# io-board-a-7.net
KiCad netlist of a schematic drawn in EAGLE
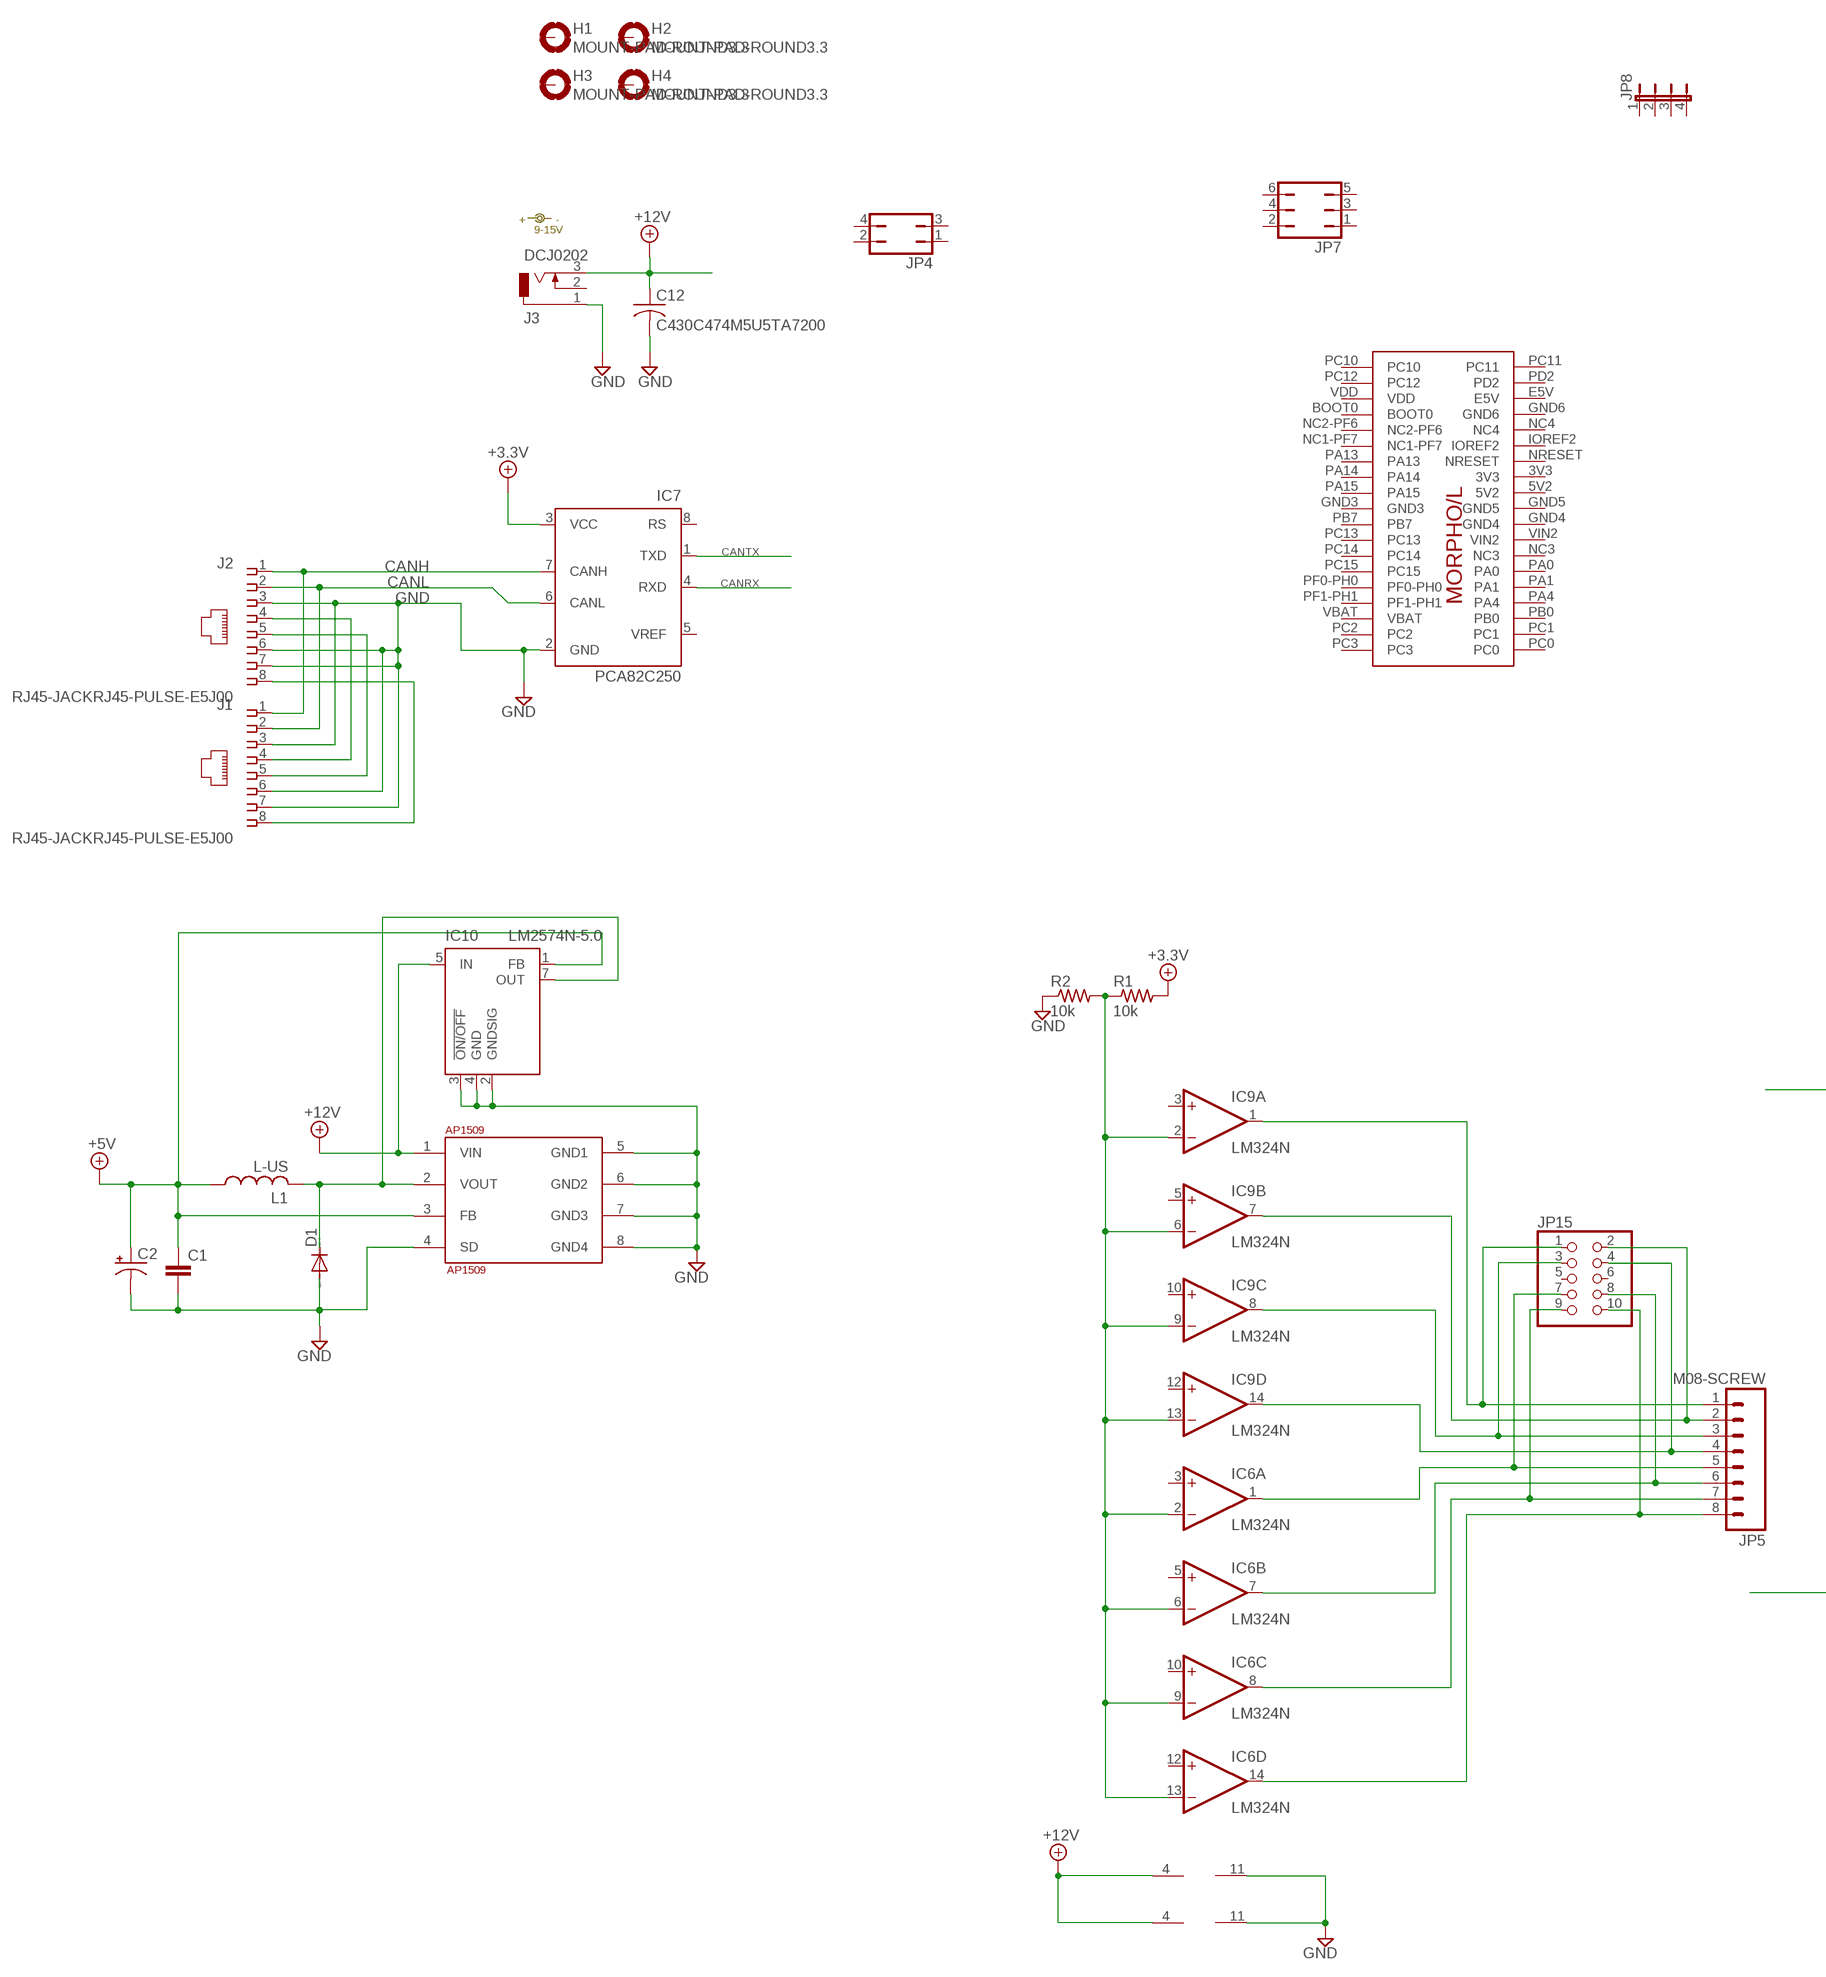
[diagram p0: schematic, sheet 1, part 1 of 2]
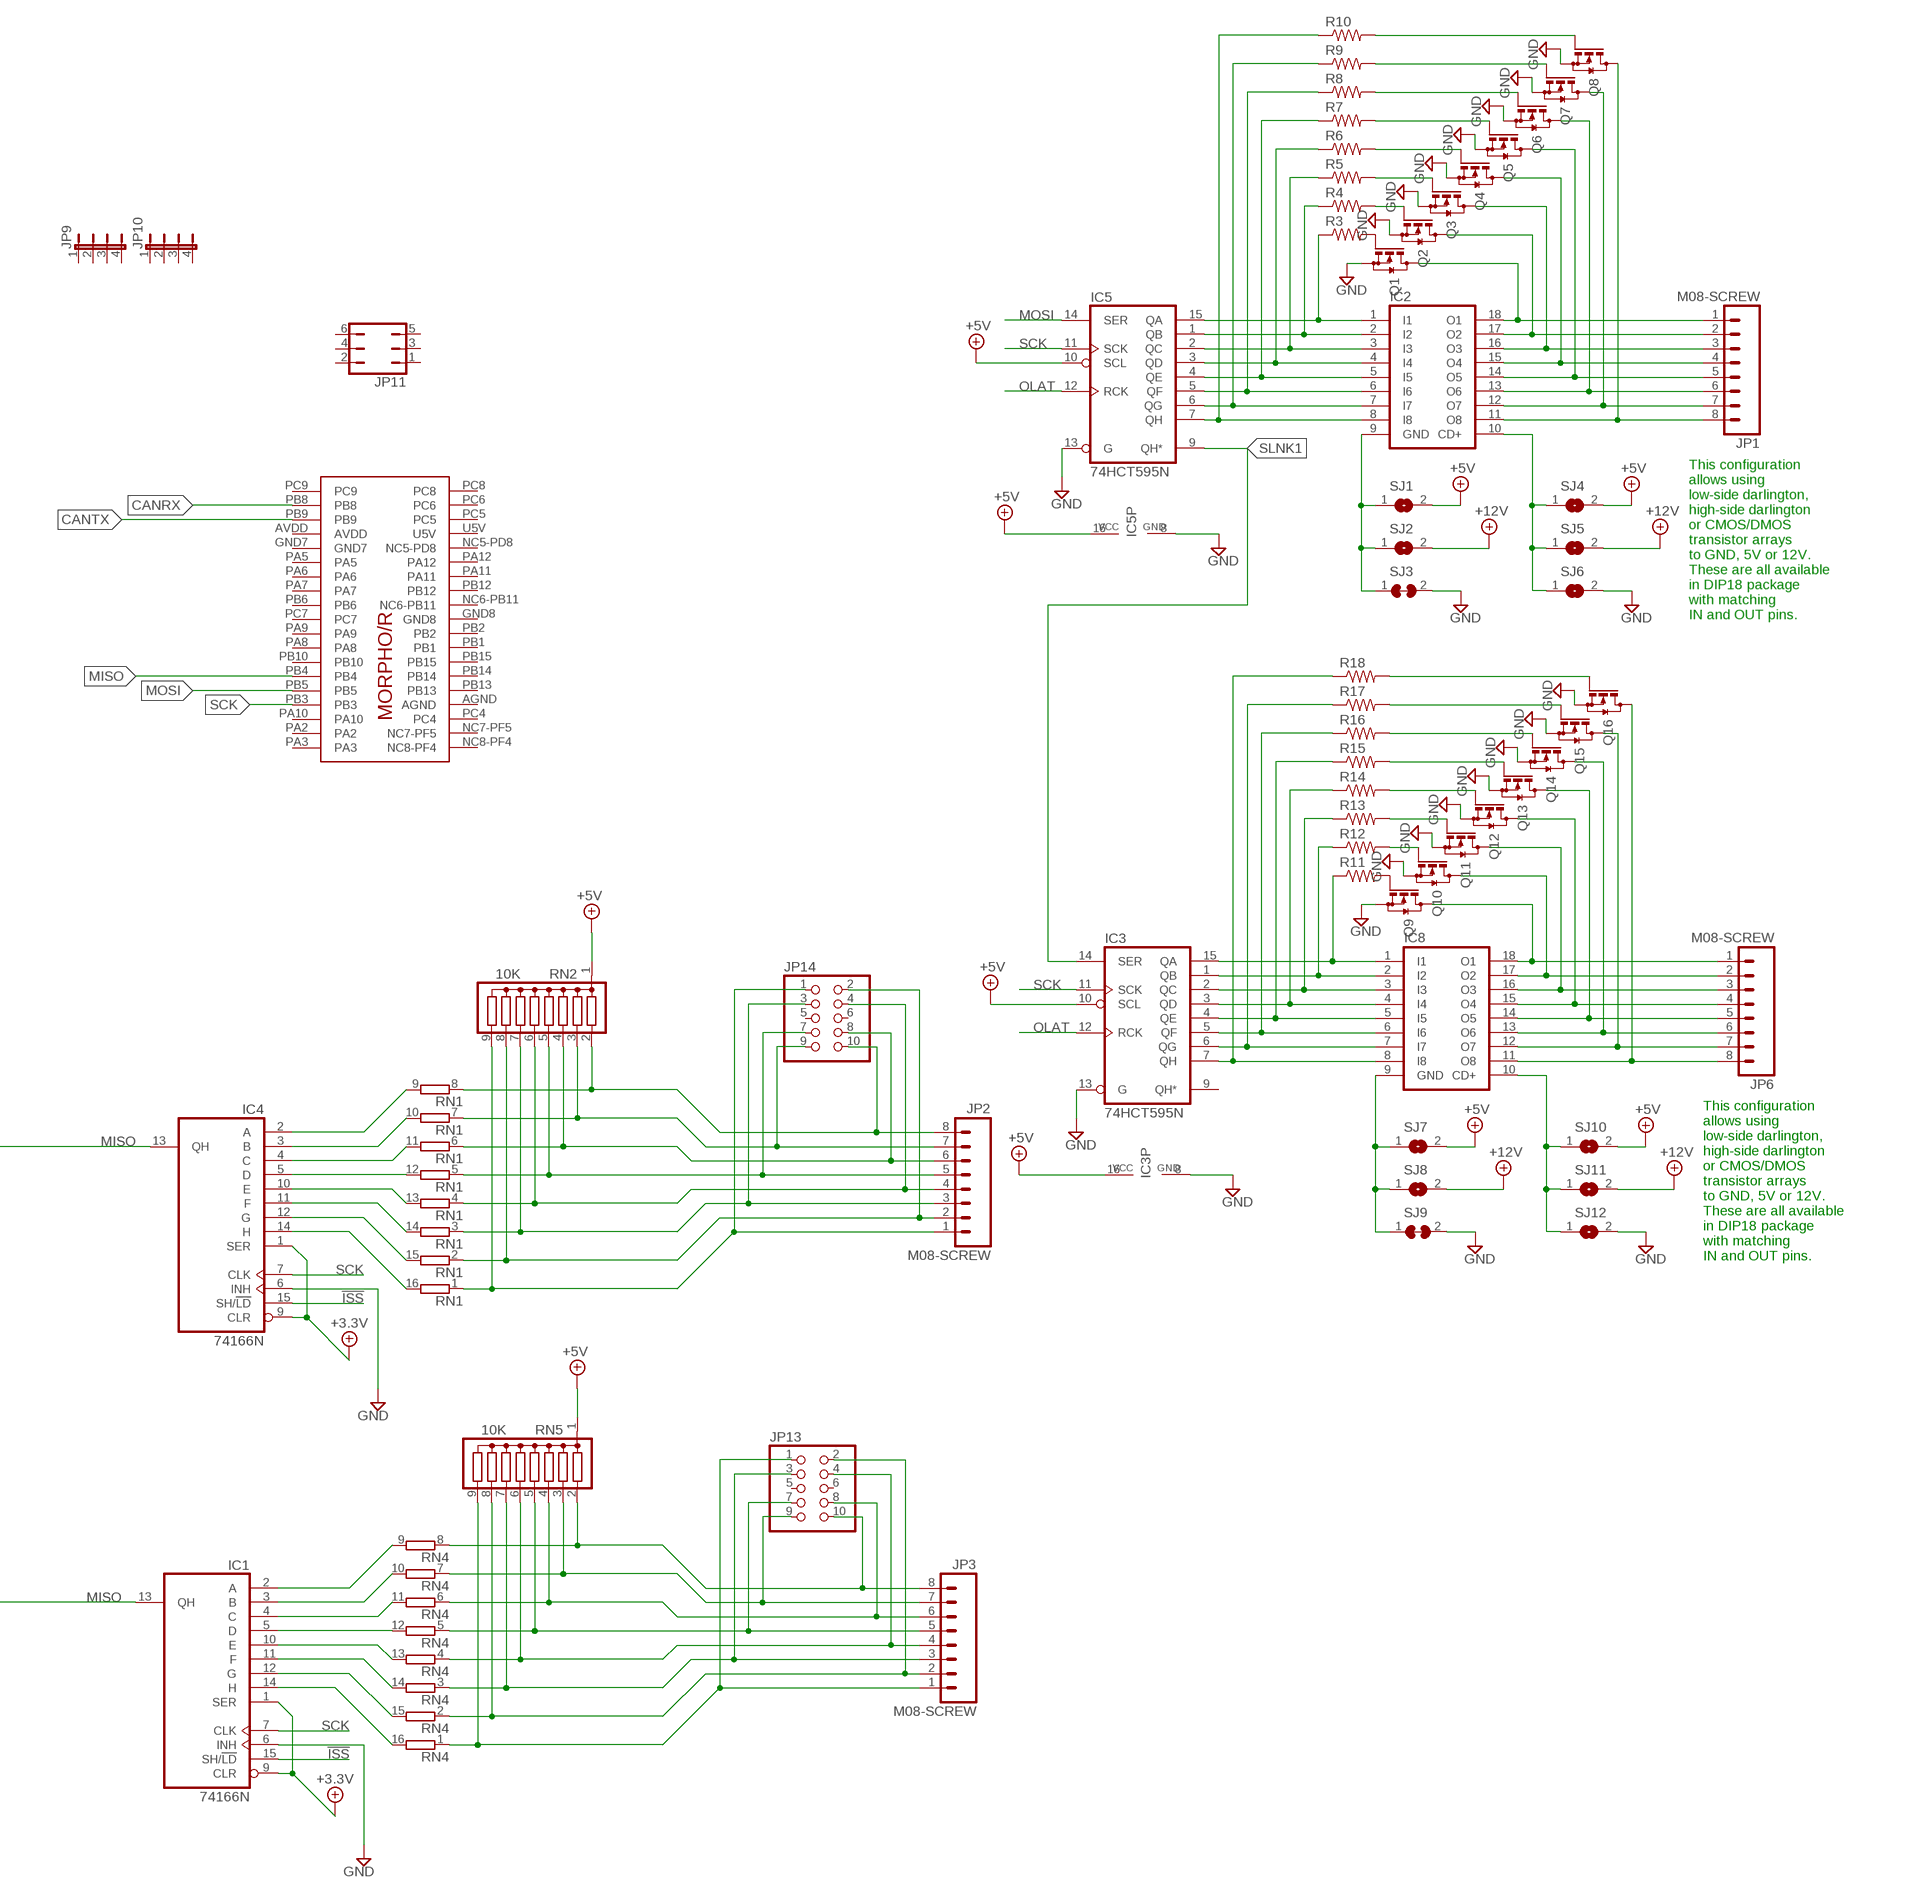
[diagram p1: schematic, sheet 1, part 2 of 2]

(export (version "E")
  (design (tool "Eeschema 10.0.6"))
  (components
    (comp (ref "+12V")
      (value "9-15V")
      (footprint "eagle-import:POWER_USAGE")
      (libsource (lib "eagle-import") (part "DOC-POWER_LABEL"))
    )
    (comp (ref "AP1509")
      (value "AP1509")
      (footprint "eagle-import:SO-08")
      (libsource (lib "eagle-import") (part "AP1509"))
    )
    (comp (ref "C1")
      (value "C-EUC1206")
      (footprint "eagle-import:C1206")
      (libsource (lib "eagle-import") (part "C-EUC1206"))
    )
    (comp (ref "C2")
      (value "CPOL-USE2.5-5")
      (footprint "eagle-import:E2,5-5")
      (libsource (lib "eagle-import") (part "CPOL-USE2.5-5"))
    )
    (comp (ref "C12")
      (value "C430C474M5U5TA7200")
      (footprint "eagle-import:C075-032X103")
      (libsource (lib "eagle-import") (part "C-US075-032X103"))
    )
    (comp (ref "D1")
      (value "DIODE-DO41-7.6")
      (footprint "eagle-import:DO41-7.6")
      (libsource (lib "eagle-import") (part "DIODE-DO41-7.6"))
    )
    (comp (ref "H1")
      (value "MOUNT-PAD-ROUND3.3")
      (footprint "eagle-import:3,3-PAD")
      (libsource (lib "eagle-import") (part "MOUNT-PAD-ROUND3.3"))
    )
    (comp (ref "H2")
      (value "MOUNT-PAD-ROUND3.3")
      (footprint "eagle-import:3,3-PAD")
      (libsource (lib "eagle-import") (part "MOUNT-PAD-ROUND3.3"))
    )
    (comp (ref "H3")
      (value "MOUNT-PAD-ROUND3.3")
      (footprint "eagle-import:3,3-PAD")
      (libsource (lib "eagle-import") (part "MOUNT-PAD-ROUND3.3"))
    )
    (comp (ref "H4")
      (value "MOUNT-PAD-ROUND3.3")
      (footprint "eagle-import:3,3-PAD")
      (libsource (lib "eagle-import") (part "MOUNT-PAD-ROUND3.3"))
    )
    (comp (ref "IC1")
      (value "74166N")
      (footprint "eagle-import:DIL16")
      (libsource (lib "eagle-import") (part "74166N"))
    )
    (comp (ref "IC2")
      (value "ULN2803A")
      (footprint "eagle-import:DIL18-THIN")
      (libsource (lib "eagle-import") (part "ULN2803A"))
    )
    (comp (ref "IC3")
      (value "74HCT595N")
      (footprint "eagle-import:DIL16")
      (libsource (lib "eagle-import") (part "74595NHCT"))
    )
    (comp (ref "IC4")
      (value "74166N")
      (footprint "eagle-import:DIL16")
      (libsource (lib "eagle-import") (part "74166N"))
    )
    (comp (ref "IC5")
      (value "74HCT595N")
      (footprint "eagle-import:DIL16")
      (libsource (lib "eagle-import") (part "74595NHCT"))
    )
    (comp (ref "IC6")
      (value "LM324N")
      (footprint "eagle-import:DIL14")
      (libsource (lib "eagle-import") (part "LM324N"))
    )
    (comp (ref "IC7")
      (value "PCA82C250")
      (footprint "eagle-import:DIL08")
      (libsource (lib "eagle-import") (part "PCA82C250"))
    )
    (comp (ref "IC8")
      (value "ULN2803A")
      (footprint "eagle-import:DIL18-THIN")
      (libsource (lib "eagle-import") (part "ULN2803A"))
    )
    (comp (ref "IC9")
      (value "LM324N")
      (footprint "eagle-import:DIL14")
      (libsource (lib "eagle-import") (part "LM324N"))
    )
    (comp (ref "IC10")
      (value "LM2574N-5.0")
      (footprint "eagle-import:DIL08")
      (libsource (lib "eagle-import") (part "LM2574?-N5.0"))
    )
    (comp (ref "J1")
      (value "RJ45-JACKRJ45-PULSE-E5J00")
      (footprint "eagle-import:RJ45-PULSE-E5J88")
      (libsource (lib "eagle-import") (part "RJ45-JACKRJ45-PULSE-E5J00"))
    )
    (comp (ref "J2")
      (value "RJ45-JACKRJ45-PULSE-E5J00")
      (footprint "eagle-import:RJ45-PULSE-E5J88")
      (libsource (lib "eagle-import") (part "RJ45-JACKRJ45-PULSE-E5J00"))
    )
    (comp (ref "J3")
      (value "DCJ0202")
      (footprint "eagle-import:DCJ0202")
      (libsource (lib "eagle-import") (part "DCJ0202"))
    )
    (comp (ref "JP1")
      (value "M08-SCREW")
      (footprint "eagle-import:1X08_TERMINAL")
      (libsource (lib "eagle-import") (part "M08-SCREW"))
    )
    (comp (ref "JP2")
      (value "M08-SCREW")
      (footprint "eagle-import:1X08_TERMINAL")
      (libsource (lib "eagle-import") (part "M08-SCREW"))
    )
    (comp (ref "JP3")
      (value "M08-SCREW")
      (footprint "eagle-import:1X08_TERMINAL")
      (libsource (lib "eagle-import") (part "M08-SCREW"))
    )
    (comp (ref "JP4")
      (value "JP2Q")
      (footprint "eagle-import:JP2Q")
      (libsource (lib "eagle-import") (part "JP2Q"))
    )
    (comp (ref "JP5")
      (value "M08-SCREW")
      (footprint "eagle-import:1X08_TERMINAL")
      (libsource (lib "eagle-import") (part "M08-SCREW"))
    )
    (comp (ref "JP6")
      (value "M08-SCREW")
      (footprint "eagle-import:1X08_TERMINAL")
      (libsource (lib "eagle-import") (part "M08-SCREW"))
    )
    (comp (ref "JP7")
      (value "JP3Q")
      (footprint "eagle-import:JP3Q")
      (libsource (lib "eagle-import") (part "JP3Q"))
    )
    (comp (ref "JP8")
      (value "JP4-FLAT")
      (footprint "eagle-import:JP4F")
      (libsource (lib "eagle-import") (part "JP4-FLAT"))
    )
    (comp (ref "JP9")
      (value "JP4-FLAT")
      (footprint "eagle-import:JP4F")
      (libsource (lib "eagle-import") (part "JP4-FLAT"))
    )
    (comp (ref "JP10")
      (value "JP4-FLAT")
      (footprint "eagle-import:JP4F")
      (libsource (lib "eagle-import") (part "JP4-FLAT"))
    )
    (comp (ref "JP11")
      (value "JP3Q")
      (footprint "eagle-import:JP3Q")
      (libsource (lib "eagle-import") (part "JP3Q"))
    )
    (comp (ref "JP13")
      (value "PINHD-2X5CN")
      (footprint "eagle-import:CON10M")
      (libsource (lib "eagle-import") (part "PINHD-2X5CN"))
    )
    (comp (ref "JP14")
      (value "PINHD-2X5CN")
      (footprint "eagle-import:CON10M")
      (libsource (lib "eagle-import") (part "PINHD-2X5CN"))
    )
    (comp (ref "JP15")
      (value "PINHD-2X5CN")
      (footprint "eagle-import:CON10M")
      (libsource (lib "eagle-import") (part "PINHD-2X5CN"))
    )
    (comp (ref "L1")
      (value "L-US")
      (footprint "eagle-import:L5-8,5")
      (libsource (lib "eagle-import") (part "L-US"))
    )
    (comp (ref "Q1")
      (value "BSS123")
      (footprint "eagle-import:SOT23")
      (libsource (lib "eagle-import") (part "BSS123"))
    )
    (comp (ref "Q2")
      (value "BSS123")
      (footprint "eagle-import:SOT23")
      (libsource (lib "eagle-import") (part "BSS123"))
    )
    (comp (ref "Q3")
      (value "BSS123")
      (footprint "eagle-import:SOT23")
      (libsource (lib "eagle-import") (part "BSS123"))
    )
    (comp (ref "Q4")
      (value "BSS123")
      (footprint "eagle-import:SOT23")
      (libsource (lib "eagle-import") (part "BSS123"))
    )
    (comp (ref "Q5")
      (value "BSS123")
      (footprint "eagle-import:SOT23")
      (libsource (lib "eagle-import") (part "BSS123"))
    )
    (comp (ref "Q6")
      (value "BSS123")
      (footprint "eagle-import:SOT23")
      (libsource (lib "eagle-import") (part "BSS123"))
    )
    (comp (ref "Q7")
      (value "BSS123")
      (footprint "eagle-import:SOT23")
      (libsource (lib "eagle-import") (part "BSS123"))
    )
    (comp (ref "Q8")
      (value "BSS123")
      (footprint "eagle-import:SOT23")
      (libsource (lib "eagle-import") (part "BSS123"))
    )
    (comp (ref "Q9")
      (value "BSS123")
      (footprint "eagle-import:SOT23")
      (libsource (lib "eagle-import") (part "BSS123"))
    )
    (comp (ref "Q10")
      (value "BSS123")
      (footprint "eagle-import:SOT23")
      (libsource (lib "eagle-import") (part "BSS123"))
    )
    (comp (ref "Q11")
      (value "BSS123")
      (footprint "eagle-import:SOT23")
      (libsource (lib "eagle-import") (part "BSS123"))
    )
    (comp (ref "Q12")
      (value "BSS123")
      (footprint "eagle-import:SOT23")
      (libsource (lib "eagle-import") (part "BSS123"))
    )
    (comp (ref "Q13")
      (value "BSS123")
      (footprint "eagle-import:SOT23")
      (libsource (lib "eagle-import") (part "BSS123"))
    )
    (comp (ref "Q14")
      (value "BSS123")
      (footprint "eagle-import:SOT23")
      (libsource (lib "eagle-import") (part "BSS123"))
    )
    (comp (ref "Q15")
      (value "BSS123")
      (footprint "eagle-import:SOT23")
      (libsource (lib "eagle-import") (part "BSS123"))
    )
    (comp (ref "Q16")
      (value "BSS123")
      (footprint "eagle-import:SOT23")
      (libsource (lib "eagle-import") (part "BSS123"))
    )
    (comp (ref "R1")
      (value "10k")
      (footprint "eagle-import:R1206")
      (libsource (lib "eagle-import") (part "R-US_R1206"))
    )
    (comp (ref "R2")
      (value "10k")
      (footprint "eagle-import:R1206")
      (libsource (lib "eagle-import") (part "R-US_R1206"))
    )
    (comp (ref "R3")
      (value "R-US_R0603")
      (footprint "eagle-import:R0603")
      (libsource (lib "eagle-import") (part "R-US_R0603"))
    )
    (comp (ref "R4")
      (value "R-US_R0603")
      (footprint "eagle-import:R0603")
      (libsource (lib "eagle-import") (part "R-US_R0603"))
    )
    (comp (ref "R5")
      (value "R-US_R0603")
      (footprint "eagle-import:R0603")
      (libsource (lib "eagle-import") (part "R-US_R0603"))
    )
    (comp (ref "R6")
      (value "R-US_R0603")
      (footprint "eagle-import:R0603")
      (libsource (lib "eagle-import") (part "R-US_R0603"))
    )
    (comp (ref "R7")
      (value "R-US_R0603")
      (footprint "eagle-import:R0603")
      (libsource (lib "eagle-import") (part "R-US_R0603"))
    )
    (comp (ref "R8")
      (value "R-US_R0603")
      (footprint "eagle-import:R0603")
      (libsource (lib "eagle-import") (part "R-US_R0603"))
    )
    (comp (ref "R9")
      (value "R-US_R0603")
      (footprint "eagle-import:R0603")
      (libsource (lib "eagle-import") (part "R-US_R0603"))
    )
    (comp (ref "R10")
      (value "R-US_R0603")
      (footprint "eagle-import:R0603")
      (libsource (lib "eagle-import") (part "R-US_R0603"))
    )
    (comp (ref "R11")
      (value "R-US_R0603")
      (footprint "eagle-import:R0603")
      (libsource (lib "eagle-import") (part "R-US_R0603"))
    )
    (comp (ref "R12")
      (value "R-US_R0603")
      (footprint "eagle-import:R0603")
      (libsource (lib "eagle-import") (part "R-US_R0603"))
    )
    (comp (ref "R13")
      (value "R-US_R0603")
      (footprint "eagle-import:R0603")
      (libsource (lib "eagle-import") (part "R-US_R0603"))
    )
    (comp (ref "R14")
      (value "R-US_R0603")
      (footprint "eagle-import:R0603")
      (libsource (lib "eagle-import") (part "R-US_R0603"))
    )
    (comp (ref "R15")
      (value "R-US_R0603")
      (footprint "eagle-import:R0603")
      (libsource (lib "eagle-import") (part "R-US_R0603"))
    )
    (comp (ref "R16")
      (value "R-US_R0603")
      (footprint "eagle-import:R0603")
      (libsource (lib "eagle-import") (part "R-US_R0603"))
    )
    (comp (ref "R17")
      (value "R-US_R0603")
      (footprint "eagle-import:R0603")
      (libsource (lib "eagle-import") (part "R-US_R0603"))
    )
    (comp (ref "R18")
      (value "R-US_R0603")
      (footprint "eagle-import:R0603")
      (libsource (lib "eagle-import") (part "R-US_R0603"))
    )
    (comp (ref "RN1")
      (value "8R-P")
      (footprint "eagle-import:DIL16")
      (libsource (lib "eagle-import") (part "8R-P"))
    )
    (comp (ref "RN2")
      (value "10K")
      (footprint "eagle-import:SIL9")
      (libsource (lib "eagle-import") (part "G08R"))
    )
    (comp (ref "RN4")
      (value "8R-P")
      (footprint "eagle-import:DIL16")
      (libsource (lib "eagle-import") (part "8R-P"))
    )
    (comp (ref "RN5")
      (value "10K")
      (footprint "eagle-import:SIL9")
      (libsource (lib "eagle-import") (part "G08R"))
    )
    (comp (ref "SJ1")
      (value "SJ")
      (footprint "eagle-import:SJ-RND")
      (libsource (lib "eagle-import") (part "SJ"))
    )
    (comp (ref "SJ2")
      (value "SJ")
      (footprint "eagle-import:SJ-RND")
      (libsource (lib "eagle-import") (part "SJ"))
    )
    (comp (ref "SJ3")
      (value "SJ-C")
      (footprint "eagle-import:SJW-C")
      (libsource (lib "eagle-import") (part "SJ-C"))
    )
    (comp (ref "SJ4")
      (value "SJ")
      (footprint "eagle-import:SJ-RND")
      (libsource (lib "eagle-import") (part "SJ"))
    )
    (comp (ref "SJ5")
      (value "SJ")
      (footprint "eagle-import:SJ-RND")
      (libsource (lib "eagle-import") (part "SJ"))
    )
    (comp (ref "SJ6")
      (value "SJ")
      (footprint "eagle-import:SJ-RND")
      (libsource (lib "eagle-import") (part "SJ"))
    )
    (comp (ref "SJ7")
      (value "SJ")
      (footprint "eagle-import:SJ-RND")
      (libsource (lib "eagle-import") (part "SJ"))
    )
    (comp (ref "SJ8")
      (value "SJ")
      (footprint "eagle-import:SJ-RND")
      (libsource (lib "eagle-import") (part "SJ"))
    )
    (comp (ref "SJ9")
      (value "SJ-C")
      (footprint "eagle-import:SJW-C")
      (libsource (lib "eagle-import") (part "SJ-C"))
    )
    (comp (ref "SJ10")
      (value "SJ")
      (footprint "eagle-import:SJ-RND")
      (libsource (lib "eagle-import") (part "SJ"))
    )
    (comp (ref "SJ11")
      (value "SJ")
      (footprint "eagle-import:SJ-RND")
      (libsource (lib "eagle-import") (part "SJ"))
    )
    (comp (ref "SJ12")
      (value "SJ")
      (footprint "eagle-import:SJ-RND")
      (libsource (lib "eagle-import") (part "SJ"))
    )
    (comp (ref "U$1")
      (value "NUCLEO_64_GENERIC")
      (footprint "eagle-import:NUCLEO_BRD_BASE64")
      (libsource (lib "eagle-import") (part "NUCLEO_64_GENERIC"))
    )
  )
  (nets
    (net (code "1") (name "+3.3V") (class "Default")
      (node (ref "IC1") (pin "1") (pinfunction "SER_1") (pintype "input"))
      (node (ref "IC1") (pin "9") (pinfunction "CLR_9") (pintype "input"))
      (node (ref "IC4") (pin "1") (pinfunction "SER_1") (pintype "input"))
      (node (ref "IC4") (pin "9") (pinfunction "CLR_9") (pintype "input"))
      (node (ref "IC7") (pin "3") (pinfunction "VCC_3") (pintype "power_in"))
      (node (ref "R1") (pin "2") (pinfunction "2_2") (pintype "passive"))
    )
    (net (code "2") (name "+5V") (class "Default")
      (node (ref "AP1509") (pin "3") (pinfunction "FB_3") (pintype "bidirectional"))
      (node (ref "C1") (pin "1") (pinfunction "1_1") (pintype "passive"))
      (node (ref "C2") (pin "+") (pinfunction "+_+") (pintype "passive"))
      (node (ref "IC10") (pin "1") (pinfunction "FB_1") (pintype "input"))
      (node (ref "IC3") (pin "10") (pinfunction "SCL_10") (pintype "input"))
      (node (ref "IC3") (pin "16") (pinfunction "VCC_16") (pintype "power_in"))
      (node (ref "IC5") (pin "10") (pinfunction "SCL_10") (pintype "input"))
      (node (ref "IC5") (pin "16") (pinfunction "VCC_16") (pintype "power_in"))
      (node (ref "L1") (pin "1") (pinfunction "1_1") (pintype "passive"))
      (node (ref "RN2") (pin "1") (pinfunction "1_1") (pintype "passive"))
      (node (ref "RN5") (pin "1") (pinfunction "1_1") (pintype "passive"))
      (node (ref "SJ1") (pin "2") (pinfunction "2_2") (pintype "passive"))
      (node (ref "SJ10") (pin "2") (pinfunction "2_2") (pintype "passive"))
      (node (ref "SJ4") (pin "2") (pinfunction "2_2") (pintype "passive"))
      (node (ref "SJ7") (pin "2") (pinfunction "2_2") (pintype "passive"))
    )
    (net (code "3") (name "+12V") (class "Default")
      (node (ref "AP1509") (pin "1") (pinfunction "VIN_1") (pintype "bidirectional"))
      (node (ref "C12") (pin "1") (pinfunction "1_1") (pintype "passive"))
      (node (ref "IC10") (pin "5") (pinfunction "IN_5") (pintype "input"))
      (node (ref "IC6") (pin "4") (pinfunction "V+_4") (pintype "power_in"))
      (node (ref "IC9") (pin "4") (pinfunction "V+_4") (pintype "power_in"))
      (node (ref "J3") (pin "3") (pinfunction "3_3") (pintype "passive"))
      (node (ref "SJ11") (pin "2") (pinfunction "2_2") (pintype "passive"))
      (node (ref "SJ2") (pin "2") (pinfunction "2_2") (pintype "passive"))
      (node (ref "SJ5") (pin "2") (pinfunction "2_2") (pintype "passive"))
      (node (ref "SJ8") (pin "2") (pinfunction "2_2") (pintype "passive"))
    )
    (net (code "4") (name "/3V3") (class "Default")
      (node (ref "U$1") (pin "3V3") (pinfunction "3V3_3V3") (pintype "power_in"))
    )
    (net (code "5") (name "/5V2") (class "Default")
      (node (ref "U$1") (pin "5V2") (pinfunction "5V2_5V2") (pintype "power_in"))
    )
    (net (code "6") (name "/AGND") (class "Default")
      (node (ref "U$1") (pin "AGND") (pinfunction "AGND_AGND") (pintype "power_in"))
    )
    (net (code "7") (name "/AVDD") (class "Default")
      (node (ref "U$1") (pin "AVDD") (pinfunction "AVDD_AVDD") (pintype "power_in"))
    )
    (net (code "8") (name "/CANH") (class "Default")
      (node (ref "IC7") (pin "7") (pinfunction "CANH_7") (pintype "bidirectional"))
      (node (ref "J1") (pin "1") (pinfunction "1_1") (pintype "passive"))
      (node (ref "J2") (pin "1") (pinfunction "1_1") (pintype "passive"))
    )
    (net (code "9") (name "/CANL") (class "Default")
      (node (ref "IC7") (pin "6") (pinfunction "CANL_6") (pintype "bidirectional"))
      (node (ref "J1") (pin "2") (pinfunction "2_2") (pintype "passive"))
      (node (ref "J2") (pin "2") (pinfunction "2_2") (pintype "passive"))
    )
    (net (code "10") (name "/E5V") (class "Default")
      (node (ref "U$1") (pin "E5V") (pinfunction "E5V_E5V") (pintype "power_in"))
    )
    (net (code "11") (name "/GND3") (class "Default")
      (node (ref "U$1") (pin "GND3") (pinfunction "GND3_GND3") (pintype "power_in"))
    )
    (net (code "12") (name "/GND4") (class "Default")
      (node (ref "U$1") (pin "GND4") (pinfunction "GND4_GND4") (pintype "power_in"))
    )
    (net (code "13") (name "/GND5") (class "Default")
      (node (ref "U$1") (pin "GND5") (pinfunction "GND5_GND5") (pintype "power_in"))
    )
    (net (code "14") (name "/GND6") (class "Default")
      (node (ref "U$1") (pin "GND6") (pinfunction "GND6_GND6") (pintype "power_in"))
    )
    (net (code "15") (name "/GND7") (class "Default")
      (node (ref "U$1") (pin "GND7") (pinfunction "GND7_GND7") (pintype "power_in"))
    )
    (net (code "16") (name "/GND8") (class "Default")
      (node (ref "U$1") (pin "GND8") (pinfunction "GND8_GND8") (pintype "power_in"))
    )
    (net (code "17") (name "/OLAT") (class "Default")
      (node (ref "IC3") (pin "12") (pinfunction "RCK_12") (pintype "input"))
      (node (ref "IC5") (pin "12") (pinfunction "RCK_12") (pintype "input"))
    )
    (net (code "18") (name "/U5V") (class "Default")
      (node (ref "U$1") (pin "U5V") (pinfunction "U5V_U5V") (pintype "power_in"))
    )
    (net (code "19") (name "/VBAT") (class "Default")
      (node (ref "U$1") (pin "VBAT") (pinfunction "VBAT_VBAT") (pintype "power_in"))
    )
    (net (code "20") (name "/VDD") (class "Default")
      (node (ref "U$1") (pin "VDD") (pinfunction "VDD_VDD") (pintype "power_in"))
    )
    (net (code "21") (name "/VIN2") (class "Default")
      (node (ref "U$1") (pin "VIN2") (pinfunction "VIN2_VIN2") (pintype "power_in"))
    )
    (net (code "22") (name "/~{ISS}") (class "Default")
      (node (ref "IC1") (pin "15") (pinfunction "SH/~{LD}_15") (pintype "input"))
      (node (ref "IC4") (pin "15") (pinfunction "SH/~{LD}_15") (pintype "input"))
    )
    (net (code "23") (name "CANRX") (class "Default")
      (node (ref "IC7") (pin "4") (pinfunction "RXD_4") (pintype "output"))
      (node (ref "U$1") (pin "PB8") (pinfunction "PB8_PB8") (pintype "bidirectional"))
    )
    (net (code "24") (name "CANTX") (class "Default")
      (node (ref "IC7") (pin "1") (pinfunction "TXD_1") (pintype "input"))
      (node (ref "U$1") (pin "PB9") (pinfunction "PB9_PB9") (pintype "bidirectional"))
    )
    (net (code "25") (name "GND") (class "Default")
      (node (ref "AP1509") (pin "4") (pinfunction "SD_4") (pintype "bidirectional"))
      (node (ref "AP1509") (pin "5") (pinfunction "GND1_5") (pintype "power_in"))
      (node (ref "AP1509") (pin "6") (pinfunction "GND2_6") (pintype "power_in"))
      (node (ref "AP1509") (pin "7") (pinfunction "GND3_7") (pintype "power_in"))
      (node (ref "AP1509") (pin "8") (pinfunction "GND4_8") (pintype "power_in"))
      (node (ref "C1") (pin "2") (pinfunction "2_2") (pintype "passive"))
      (node (ref "C12") (pin "2") (pinfunction "2_2") (pintype "passive"))
      (node (ref "C2") (pin "-") (pinfunction "-_-") (pintype "passive"))
      (node (ref "D1") (pin "A") (pinfunction "A_A") (pintype "passive"))
      (node (ref "IC1") (pin "6") (pinfunction "INH_6") (pintype "input"))
      (node (ref "IC10") (pin "2") (pinfunction "GNDSIG_2") (pintype "input"))
      (node (ref "IC10") (pin "3") (pinfunction "~{ON/OFF}_3") (pintype "input"))
      (node (ref "IC10") (pin "4") (pinfunction "GND_4") (pintype "power_in"))
      (node (ref "IC3") (pin "13") (pinfunction "G_13") (pintype "input"))
      (node (ref "IC3") (pin "8") (pinfunction "GND_8") (pintype "power_in"))
      (node (ref "IC4") (pin "6") (pinfunction "INH_6") (pintype "input"))
      (node (ref "IC5") (pin "13") (pinfunction "G_13") (pintype "input"))
      (node (ref "IC5") (pin "8") (pinfunction "GND_8") (pintype "power_in"))
      (node (ref "IC6") (pin "11") (pinfunction "V-_11") (pintype "power_in"))
      (node (ref "IC7") (pin "2") (pinfunction "GND_2") (pintype "power_in"))
      (node (ref "IC9") (pin "11") (pinfunction "V-_11") (pintype "power_in"))
      (node (ref "J1") (pin "3") (pinfunction "3_3") (pintype "passive"))
      (node (ref "J1") (pin "6") (pinfunction "6_6") (pintype "passive"))
      (node (ref "J1") (pin "7") (pinfunction "7_7") (pintype "passive"))
      (node (ref "J2") (pin "3") (pinfunction "3_3") (pintype "passive"))
      (node (ref "J2") (pin "6") (pinfunction "6_6") (pintype "passive"))
      (node (ref "J2") (pin "7") (pinfunction "7_7") (pintype "passive"))
      (node (ref "J3") (pin "1") (pinfunction "1_1") (pintype "passive"))
      (node (ref "Q1") (pin "2") (pinfunction "S_2") (pintype "passive"))
      (node (ref "Q10") (pin "2") (pinfunction "S_2") (pintype "passive"))
      (node (ref "Q11") (pin "2") (pinfunction "S_2") (pintype "passive"))
      (node (ref "Q12") (pin "2") (pinfunction "S_2") (pintype "passive"))
      (node (ref "Q13") (pin "2") (pinfunction "S_2") (pintype "passive"))
      (node (ref "Q14") (pin "2") (pinfunction "S_2") (pintype "passive"))
      (node (ref "Q15") (pin "2") (pinfunction "S_2") (pintype "passive"))
      (node (ref "Q16") (pin "2") (pinfunction "S_2") (pintype "passive"))
      (node (ref "Q2") (pin "2") (pinfunction "S_2") (pintype "passive"))
      (node (ref "Q3") (pin "2") (pinfunction "S_2") (pintype "passive"))
      (node (ref "Q4") (pin "2") (pinfunction "S_2") (pintype "passive"))
      (node (ref "Q5") (pin "2") (pinfunction "S_2") (pintype "passive"))
      (node (ref "Q6") (pin "2") (pinfunction "S_2") (pintype "passive"))
      (node (ref "Q7") (pin "2") (pinfunction "S_2") (pintype "passive"))
      (node (ref "Q8") (pin "2") (pinfunction "S_2") (pintype "passive"))
      (node (ref "Q9") (pin "2") (pinfunction "S_2") (pintype "passive"))
      (node (ref "R2") (pin "1") (pinfunction "1_1") (pintype "passive"))
      (node (ref "SJ12") (pin "2") (pinfunction "2_2") (pintype "passive"))
      (node (ref "SJ3") (pin "2") (pinfunction "2_2") (pintype "passive"))
      (node (ref "SJ6") (pin "2") (pinfunction "2_2") (pintype "passive"))
      (node (ref "SJ9") (pin "2") (pinfunction "2_2") (pintype "passive"))
    )
    (net (code "26") (name "MISO") (class "Default")
      (node (ref "IC1") (pin "13") (pinfunction "QH_13") (pintype "output"))
      (node (ref "IC4") (pin "13") (pinfunction "QH_13") (pintype "output"))
      (node (ref "U$1") (pin "PB4") (pinfunction "PB4_PB4") (pintype "bidirectional"))
    )
    (net (code "27") (name "MOSI") (class "Default")
      (node (ref "IC5") (pin "14") (pinfunction "SER_14") (pintype "input"))
      (node (ref "U$1") (pin "PB5") (pinfunction "PB5_PB5") (pintype "bidirectional"))
    )
    (net (code "28") (name "Net-(AP1509-VOUT)") (class "Default")
      (node (ref "AP1509") (pin "2") (pinfunction "VOUT_2") (pintype "bidirectional"))
      (node (ref "D1") (pin "C") (pinfunction "C_C") (pintype "passive"))
      (node (ref "IC10") (pin "7") (pinfunction "OUT_7") (pintype "passive"))
      (node (ref "L1") (pin "2") (pinfunction "2_2") (pintype "passive"))
    )
    (net (code "29") (name "Net-(IC1A-A)") (class "Default")
      (node (ref "IC1") (pin "2") (pinfunction "A_2") (pintype "input"))
      (node (ref "RN4") (pin "9") (pinfunction "2_9") (pintype "passive"))
    )
    (net (code "30") (name "Net-(IC1A-B)") (class "Default")
      (node (ref "IC1") (pin "3") (pinfunction "B_3") (pintype "input"))
      (node (ref "RN4") (pin "10") (pinfunction "2_10") (pintype "passive"))
    )
    (net (code "31") (name "Net-(IC1A-C)") (class "Default")
      (node (ref "IC1") (pin "4") (pinfunction "C_4") (pintype "input"))
      (node (ref "RN4") (pin "11") (pinfunction "2_11") (pintype "passive"))
    )
    (net (code "32") (name "Net-(IC1A-D)") (class "Default")
      (node (ref "IC1") (pin "5") (pinfunction "D_5") (pintype "input"))
      (node (ref "RN4") (pin "12") (pinfunction "2_12") (pintype "passive"))
    )
    (net (code "33") (name "Net-(IC1A-E)") (class "Default")
      (node (ref "IC1") (pin "10") (pinfunction "E_10") (pintype "input"))
      (node (ref "RN4") (pin "13") (pinfunction "2_13") (pintype "passive"))
    )
    (net (code "34") (name "Net-(IC1A-F)") (class "Default")
      (node (ref "IC1") (pin "11") (pinfunction "F_11") (pintype "input"))
      (node (ref "RN4") (pin "14") (pinfunction "2_14") (pintype "passive"))
    )
    (net (code "35") (name "Net-(IC1A-G)") (class "Default")
      (node (ref "IC1") (pin "12") (pinfunction "G_12") (pintype "input"))
      (node (ref "RN4") (pin "15") (pinfunction "2_15") (pintype "passive"))
    )
    (net (code "36") (name "Net-(IC1A-H)") (class "Default")
      (node (ref "IC1") (pin "14") (pinfunction "H_14") (pintype "input"))
      (node (ref "RN4") (pin "16") (pinfunction "2_16") (pintype "passive"))
    )
    (net (code "37") (name "Net-(IC2-CD+)") (class "Default")
      (node (ref "IC2") (pin "10") (pinfunction "CD+_10") (pintype "passive"))
      (node (ref "SJ4") (pin "1") (pinfunction "1_1") (pintype "passive"))
      (node (ref "SJ5") (pin "1") (pinfunction "1_1") (pintype "passive"))
      (node (ref "SJ6") (pin "1") (pinfunction "1_1") (pintype "passive"))
    )
    (net (code "38") (name "Net-(IC2-GND)") (class "Default")
      (node (ref "IC2") (pin "9") (pinfunction "GND_9") (pintype "power_in"))
      (node (ref "SJ1") (pin "1") (pinfunction "1_1") (pintype "passive"))
      (node (ref "SJ2") (pin "1") (pinfunction "1_1") (pintype "passive"))
      (node (ref "SJ3") (pin "1") (pinfunction "1_1") (pintype "passive"))
    )
    (net (code "39") (name "Net-(IC2-I1)") (class "Default")
      (node (ref "IC2") (pin "1") (pinfunction "I1_1") (pintype "input"))
      (node (ref "IC5") (pin "15") (pinfunction "QA_15") (pintype "tri_state"))
      (node (ref "R3") (pin "1") (pinfunction "1_1") (pintype "passive"))
    )
    (net (code "40") (name "Net-(IC2-I2)") (class "Default")
      (node (ref "IC2") (pin "2") (pinfunction "I2_2") (pintype "input"))
      (node (ref "IC5") (pin "1") (pinfunction "QB_1") (pintype "tri_state"))
      (node (ref "R4") (pin "1") (pinfunction "1_1") (pintype "passive"))
    )
    (net (code "41") (name "Net-(IC2-I3)") (class "Default")
      (node (ref "IC2") (pin "3") (pinfunction "I3_3") (pintype "input"))
      (node (ref "IC5") (pin "2") (pinfunction "QC_2") (pintype "tri_state"))
      (node (ref "R5") (pin "1") (pinfunction "1_1") (pintype "passive"))
    )
    (net (code "42") (name "Net-(IC2-I4)") (class "Default")
      (node (ref "IC2") (pin "4") (pinfunction "I4_4") (pintype "input"))
      (node (ref "IC5") (pin "3") (pinfunction "QD_3") (pintype "tri_state"))
      (node (ref "R6") (pin "1") (pinfunction "1_1") (pintype "passive"))
    )
    (net (code "43") (name "Net-(IC2-I5)") (class "Default")
      (node (ref "IC2") (pin "5") (pinfunction "I5_5") (pintype "input"))
      (node (ref "IC5") (pin "4") (pinfunction "QE_4") (pintype "tri_state"))
      (node (ref "R7") (pin "1") (pinfunction "1_1") (pintype "passive"))
    )
    (net (code "44") (name "Net-(IC2-I6)") (class "Default")
      (node (ref "IC2") (pin "6") (pinfunction "I6_6") (pintype "input"))
      (node (ref "IC5") (pin "5") (pinfunction "QF_5") (pintype "tri_state"))
      (node (ref "R8") (pin "1") (pinfunction "1_1") (pintype "passive"))
    )
    (net (code "45") (name "Net-(IC2-I7)") (class "Default")
      (node (ref "IC2") (pin "7") (pinfunction "I7_7") (pintype "input"))
      (node (ref "IC5") (pin "6") (pinfunction "QG_6") (pintype "tri_state"))
      (node (ref "R9") (pin "1") (pinfunction "1_1") (pintype "passive"))
    )
    (net (code "46") (name "Net-(IC2-I8)") (class "Default")
      (node (ref "IC2") (pin "8") (pinfunction "I8_8") (pintype "input"))
      (node (ref "IC5") (pin "7") (pinfunction "QH_7") (pintype "tri_state"))
      (node (ref "R10") (pin "1") (pinfunction "1_1") (pintype "passive"))
    )
    (net (code "47") (name "Net-(IC2-O1)") (class "Default")
      (node (ref "IC2") (pin "18") (pinfunction "O1_18") (pintype "open_collector"))
      (node (ref "JP1") (pin "1") (pinfunction "1_1") (pintype "passive"))
      (node (ref "Q1") (pin "3") (pinfunction "D_3") (pintype "passive"))
    )
    (net (code "48") (name "Net-(IC2-O2)") (class "Default")
      (node (ref "IC2") (pin "17") (pinfunction "O2_17") (pintype "open_collector"))
      (node (ref "JP1") (pin "2") (pinfunction "2_2") (pintype "passive"))
      (node (ref "Q2") (pin "3") (pinfunction "D_3") (pintype "passive"))
    )
    (net (code "49") (name "Net-(IC2-O3)") (class "Default")
      (node (ref "IC2") (pin "16") (pinfunction "O3_16") (pintype "open_collector"))
      (node (ref "JP1") (pin "3") (pinfunction "3_3") (pintype "passive"))
      (node (ref "Q3") (pin "3") (pinfunction "D_3") (pintype "passive"))
    )
    (net (code "50") (name "Net-(IC2-O4)") (class "Default")
      (node (ref "IC2") (pin "15") (pinfunction "O4_15") (pintype "open_collector"))
      (node (ref "JP1") (pin "4") (pinfunction "4_4") (pintype "passive"))
      (node (ref "Q4") (pin "3") (pinfunction "D_3") (pintype "passive"))
    )
    (net (code "51") (name "Net-(IC2-O5)") (class "Default")
      (node (ref "IC2") (pin "14") (pinfunction "O5_14") (pintype "open_collector"))
      (node (ref "JP1") (pin "5") (pinfunction "5_5") (pintype "passive"))
      (node (ref "Q5") (pin "3") (pinfunction "D_3") (pintype "passive"))
    )
    (net (code "52") (name "Net-(IC2-O6)") (class "Default")
      (node (ref "IC2") (pin "13") (pinfunction "O6_13") (pintype "open_collector"))
      (node (ref "JP1") (pin "6") (pinfunction "6_6") (pintype "passive"))
      (node (ref "Q6") (pin "3") (pinfunction "D_3") (pintype "passive"))
    )
    (net (code "53") (name "Net-(IC2-O7)") (class "Default")
      (node (ref "IC2") (pin "12") (pinfunction "O7_12") (pintype "open_collector"))
      (node (ref "JP1") (pin "7") (pinfunction "7_7") (pintype "passive"))
      (node (ref "Q7") (pin "3") (pinfunction "D_3") (pintype "passive"))
    )
    (net (code "54") (name "Net-(IC2-O8)") (class "Default")
      (node (ref "IC2") (pin "11") (pinfunction "O8_11") (pintype "open_collector"))
      (node (ref "JP1") (pin "8") (pinfunction "8_8") (pintype "passive"))
      (node (ref "Q8") (pin "3") (pinfunction "D_3") (pintype "passive"))
    )
    (net (code "55") (name "Net-(IC3A-QA)") (class "Default")
      (node (ref "IC3") (pin "15") (pinfunction "QA_15") (pintype "tri_state"))
      (node (ref "IC8") (pin "1") (pinfunction "I1_1") (pintype "input"))
      (node (ref "R11") (pin "1") (pinfunction "1_1") (pintype "passive"))
    )
    (net (code "56") (name "Net-(IC3A-QB)") (class "Default")
      (node (ref "IC3") (pin "1") (pinfunction "QB_1") (pintype "tri_state"))
      (node (ref "IC8") (pin "2") (pinfunction "I2_2") (pintype "input"))
      (node (ref "R12") (pin "1") (pinfunction "1_1") (pintype "passive"))
    )
    (net (code "57") (name "Net-(IC3A-QC)") (class "Default")
      (node (ref "IC3") (pin "2") (pinfunction "QC_2") (pintype "tri_state"))
      (node (ref "IC8") (pin "3") (pinfunction "I3_3") (pintype "input"))
      (node (ref "R13") (pin "1") (pinfunction "1_1") (pintype "passive"))
    )
    (net (code "58") (name "Net-(IC3A-QD)") (class "Default")
      (node (ref "IC3") (pin "3") (pinfunction "QD_3") (pintype "tri_state"))
      (node (ref "IC8") (pin "4") (pinfunction "I4_4") (pintype "input"))
      (node (ref "R14") (pin "1") (pinfunction "1_1") (pintype "passive"))
    )
    (net (code "59") (name "Net-(IC3A-QE)") (class "Default")
      (node (ref "IC3") (pin "4") (pinfunction "QE_4") (pintype "tri_state"))
      (node (ref "IC8") (pin "5") (pinfunction "I5_5") (pintype "input"))
      (node (ref "R15") (pin "1") (pinfunction "1_1") (pintype "passive"))
    )
    (net (code "60") (name "Net-(IC3A-QF)") (class "Default")
      (node (ref "IC3") (pin "5") (pinfunction "QF_5") (pintype "tri_state"))
      (node (ref "IC8") (pin "6") (pinfunction "I6_6") (pintype "input"))
      (node (ref "R16") (pin "1") (pinfunction "1_1") (pintype "passive"))
    )
    (net (code "61") (name "Net-(IC3A-QG)") (class "Default")
      (node (ref "IC3") (pin "6") (pinfunction "QG_6") (pintype "tri_state"))
      (node (ref "IC8") (pin "7") (pinfunction "I7_7") (pintype "input"))
      (node (ref "R17") (pin "1") (pinfunction "1_1") (pintype "passive"))
    )
    (net (code "62") (name "Net-(IC3A-QH)") (class "Default")
      (node (ref "IC3") (pin "7") (pinfunction "QH_7") (pintype "tri_state"))
      (node (ref "IC8") (pin "8") (pinfunction "I8_8") (pintype "input"))
      (node (ref "R18") (pin "1") (pinfunction "1_1") (pintype "passive"))
    )
    (net (code "63") (name "Net-(IC4A-A)") (class "Default")
      (node (ref "IC4") (pin "2") (pinfunction "A_2") (pintype "input"))
      (node (ref "RN1") (pin "9") (pinfunction "2_9") (pintype "passive"))
    )
    (net (code "64") (name "Net-(IC4A-B)") (class "Default")
      (node (ref "IC4") (pin "3") (pinfunction "B_3") (pintype "input"))
      (node (ref "RN1") (pin "10") (pinfunction "2_10") (pintype "passive"))
    )
    (net (code "65") (name "Net-(IC4A-C)") (class "Default")
      (node (ref "IC4") (pin "4") (pinfunction "C_4") (pintype "input"))
      (node (ref "RN1") (pin "11") (pinfunction "2_11") (pintype "passive"))
    )
    (net (code "66") (name "Net-(IC4A-D)") (class "Default")
      (node (ref "IC4") (pin "5") (pinfunction "D_5") (pintype "input"))
      (node (ref "RN1") (pin "12") (pinfunction "2_12") (pintype "passive"))
    )
    (net (code "67") (name "Net-(IC4A-E)") (class "Default")
      (node (ref "IC4") (pin "10") (pinfunction "E_10") (pintype "input"))
      (node (ref "RN1") (pin "13") (pinfunction "2_13") (pintype "passive"))
    )
    (net (code "68") (name "Net-(IC4A-F)") (class "Default")
      (node (ref "IC4") (pin "11") (pinfunction "F_11") (pintype "input"))
      (node (ref "RN1") (pin "14") (pinfunction "2_14") (pintype "passive"))
    )
    (net (code "69") (name "Net-(IC4A-G)") (class "Default")
      (node (ref "IC4") (pin "12") (pinfunction "G_12") (pintype "input"))
      (node (ref "RN1") (pin "15") (pinfunction "2_15") (pintype "passive"))
    )
    (net (code "70") (name "Net-(IC4A-H)") (class "Default")
      (node (ref "IC4") (pin "14") (pinfunction "H_14") (pintype "input"))
      (node (ref "RN1") (pin "16") (pinfunction "2_16") (pintype "passive"))
    )
    (net (code "71") (name "Net-(IC6A--IN)") (class "Default")
      (node (ref "IC6") (pin "13") (pinfunction "-IN_13") (pintype "input"))
      (node (ref "IC6") (pin "2") (pinfunction "-IN_2") (pintype "input"))
      (node (ref "IC6") (pin "6") (pinfunction "-IN_6") (pintype "input"))
      (node (ref "IC6") (pin "9") (pinfunction "-IN_9") (pintype "input"))
      (node (ref "IC9") (pin "13") (pinfunction "-IN_13") (pintype "input"))
      (node (ref "IC9") (pin "2") (pinfunction "-IN_2") (pintype "input"))
      (node (ref "IC9") (pin "6") (pinfunction "-IN_6") (pintype "input"))
      (node (ref "IC9") (pin "9") (pinfunction "-IN_9") (pintype "input"))
      (node (ref "R1") (pin "1") (pinfunction "1_1") (pintype "passive"))
      (node (ref "R2") (pin "2") (pinfunction "2_2") (pintype "passive"))
    )
    (net (code "72") (name "Net-(IC6A-OUT)") (class "Default")
      (node (ref "IC6") (pin "1") (pinfunction "OUT_1") (pintype "output"))
      (node (ref "JP15") (pin "7") (pinfunction "7_7") (pintype "passive"))
      (node (ref "JP5") (pin "5") (pinfunction "5_5") (pintype "passive"))
    )
    (net (code "73") (name "Net-(IC6B-OUT)") (class "Default")
      (node (ref "IC6") (pin "7") (pinfunction "OUT_7") (pintype "output"))
      (node (ref "JP15") (pin "8") (pinfunction "8_8") (pintype "passive"))
      (node (ref "JP5") (pin "6") (pinfunction "6_6") (pintype "passive"))
    )
    (net (code "74") (name "Net-(IC6C-OUT)") (class "Default")
      (node (ref "IC6") (pin "8") (pinfunction "OUT_8") (pintype "output"))
      (node (ref "JP15") (pin "9") (pinfunction "9_9") (pintype "passive"))
      (node (ref "JP5") (pin "7") (pinfunction "7_7") (pintype "passive"))
    )
    (net (code "75") (name "Net-(IC6D-OUT)") (class "Default")
      (node (ref "IC6") (pin "14") (pinfunction "OUT_14") (pintype "output"))
      (node (ref "JP15") (pin "10") (pinfunction "10_10") (pintype "passive"))
      (node (ref "JP5") (pin "8") (pinfunction "8_8") (pintype "passive"))
    )
    (net (code "76") (name "Net-(IC8-CD+)") (class "Default")
      (node (ref "IC8") (pin "10") (pinfunction "CD+_10") (pintype "passive"))
      (node (ref "SJ10") (pin "1") (pinfunction "1_1") (pintype "passive"))
      (node (ref "SJ11") (pin "1") (pinfunction "1_1") (pintype "passive"))
      (node (ref "SJ12") (pin "1") (pinfunction "1_1") (pintype "passive"))
    )
    (net (code "77") (name "Net-(IC8-GND)") (class "Default")
      (node (ref "IC8") (pin "9") (pinfunction "GND_9") (pintype "power_in"))
      (node (ref "SJ7") (pin "1") (pinfunction "1_1") (pintype "passive"))
      (node (ref "SJ8") (pin "1") (pinfunction "1_1") (pintype "passive"))
      (node (ref "SJ9") (pin "1") (pinfunction "1_1") (pintype "passive"))
    )
    (net (code "78") (name "Net-(IC8-O1)") (class "Default")
      (node (ref "IC8") (pin "18") (pinfunction "O1_18") (pintype "open_collector"))
      (node (ref "JP6") (pin "1") (pinfunction "1_1") (pintype "passive"))
      (node (ref "Q9") (pin "3") (pinfunction "D_3") (pintype "passive"))
    )
    (net (code "79") (name "Net-(IC8-O2)") (class "Default")
      (node (ref "IC8") (pin "17") (pinfunction "O2_17") (pintype "open_collector"))
      (node (ref "JP6") (pin "2") (pinfunction "2_2") (pintype "passive"))
      (node (ref "Q10") (pin "3") (pinfunction "D_3") (pintype "passive"))
    )
    (net (code "80") (name "Net-(IC8-O3)") (class "Default")
      (node (ref "IC8") (pin "16") (pinfunction "O3_16") (pintype "open_collector"))
      (node (ref "JP6") (pin "3") (pinfunction "3_3") (pintype "passive"))
      (node (ref "Q11") (pin "3") (pinfunction "D_3") (pintype "passive"))
    )
    (net (code "81") (name "Net-(IC8-O4)") (class "Default")
      (node (ref "IC8") (pin "15") (pinfunction "O4_15") (pintype "open_collector"))
      (node (ref "JP6") (pin "4") (pinfunction "4_4") (pintype "passive"))
      (node (ref "Q12") (pin "3") (pinfunction "D_3") (pintype "passive"))
    )
    (net (code "82") (name "Net-(IC8-O5)") (class "Default")
      (node (ref "IC8") (pin "14") (pinfunction "O5_14") (pintype "open_collector"))
      (node (ref "JP6") (pin "5") (pinfunction "5_5") (pintype "passive"))
      (node (ref "Q13") (pin "3") (pinfunction "D_3") (pintype "passive"))
    )
    (net (code "83") (name "Net-(IC8-O6)") (class "Default")
      (node (ref "IC8") (pin "13") (pinfunction "O6_13") (pintype "open_collector"))
      (node (ref "JP6") (pin "6") (pinfunction "6_6") (pintype "passive"))
      (node (ref "Q14") (pin "3") (pinfunction "D_3") (pintype "passive"))
    )
    (net (code "84") (name "Net-(IC8-O7)") (class "Default")
      (node (ref "IC8") (pin "12") (pinfunction "O7_12") (pintype "open_collector"))
      (node (ref "JP6") (pin "7") (pinfunction "7_7") (pintype "passive"))
      (node (ref "Q15") (pin "3") (pinfunction "D_3") (pintype "passive"))
    )
    (net (code "85") (name "Net-(IC8-O8)") (class "Default")
      (node (ref "IC8") (pin "11") (pinfunction "O8_11") (pintype "open_collector"))
      (node (ref "JP6") (pin "8") (pinfunction "8_8") (pintype "passive"))
      (node (ref "Q16") (pin "3") (pinfunction "D_3") (pintype "passive"))
    )
    (net (code "86") (name "Net-(IC9A-OUT)") (class "Default")
      (node (ref "IC9") (pin "1") (pinfunction "OUT_1") (pintype "output"))
      (node (ref "JP15") (pin "1") (pinfunction "1_1") (pintype "passive"))
      (node (ref "JP5") (pin "1") (pinfunction "1_1") (pintype "passive"))
    )
    (net (code "87") (name "Net-(IC9B-OUT)") (class "Default")
      (node (ref "IC9") (pin "7") (pinfunction "OUT_7") (pintype "output"))
      (node (ref "JP15") (pin "2") (pinfunction "2_2") (pintype "passive"))
      (node (ref "JP5") (pin "2") (pinfunction "2_2") (pintype "passive"))
    )
    (net (code "88") (name "Net-(IC9C-OUT)") (class "Default")
      (node (ref "IC9") (pin "8") (pinfunction "OUT_8") (pintype "output"))
      (node (ref "JP15") (pin "3") (pinfunction "3_3") (pintype "passive"))
      (node (ref "JP5") (pin "3") (pinfunction "3_3") (pintype "passive"))
    )
    (net (code "89") (name "Net-(IC9D-OUT)") (class "Default")
      (node (ref "IC9") (pin "14") (pinfunction "OUT_14") (pintype "output"))
      (node (ref "JP15") (pin "4") (pinfunction "4_4") (pintype "passive"))
      (node (ref "JP5") (pin "4") (pinfunction "4_4") (pintype "passive"))
    )
    (net (code "90") (name "Net-(J1-Pad4)") (class "Default")
      (node (ref "J1") (pin "4") (pinfunction "4_4") (pintype "passive"))
      (node (ref "J2") (pin "4") (pinfunction "4_4") (pintype "passive"))
    )
    (net (code "91") (name "Net-(J1-Pad5)") (class "Default")
      (node (ref "J1") (pin "5") (pinfunction "5_5") (pintype "passive"))
      (node (ref "J2") (pin "5") (pinfunction "5_5") (pintype "passive"))
    )
    (net (code "92") (name "Net-(J1-Pad8)") (class "Default")
      (node (ref "J1") (pin "8") (pinfunction "8_8") (pintype "passive"))
      (node (ref "J2") (pin "8") (pinfunction "8_8") (pintype "passive"))
    )
    (net (code "93") (name "Net-(JP13-Pad1)") (class "Default")
      (node (ref "JP13") (pin "1") (pinfunction "1_1") (pintype "passive"))
      (node (ref "JP3") (pin "1") (pinfunction "1_1") (pintype "passive"))
      (node (ref "RN4") (pin "1") (pinfunction "1_1") (pintype "passive"))
      (node (ref "RN5") (pin "9") (pinfunction "9_9") (pintype "passive"))
    )
    (net (code "94") (name "Net-(JP14-Pad1)") (class "Default")
      (node (ref "JP14") (pin "1") (pinfunction "1_1") (pintype "passive"))
      (node (ref "JP2") (pin "1") (pinfunction "1_1") (pintype "passive"))
      (node (ref "RN1") (pin "1") (pinfunction "1_1") (pintype "passive"))
      (node (ref "RN2") (pin "9") (pinfunction "9_9") (pintype "passive"))
    )
    (net (code "95") (name "Net-(Q1-G)") (class "Default")
      (node (ref "Q1") (pin "1") (pinfunction "G_1") (pintype "passive"))
      (node (ref "R3") (pin "2") (pinfunction "2_2") (pintype "passive"))
    )
    (net (code "96") (name "Net-(Q2-G)") (class "Default")
      (node (ref "Q2") (pin "1") (pinfunction "G_1") (pintype "passive"))
      (node (ref "R4") (pin "2") (pinfunction "2_2") (pintype "passive"))
    )
    (net (code "97") (name "Net-(Q3-G)") (class "Default")
      (node (ref "Q3") (pin "1") (pinfunction "G_1") (pintype "passive"))
      (node (ref "R5") (pin "2") (pinfunction "2_2") (pintype "passive"))
    )
    (net (code "98") (name "Net-(Q4-G)") (class "Default")
      (node (ref "Q4") (pin "1") (pinfunction "G_1") (pintype "passive"))
      (node (ref "R6") (pin "2") (pinfunction "2_2") (pintype "passive"))
    )
    (net (code "99") (name "Net-(Q5-G)") (class "Default")
      (node (ref "Q5") (pin "1") (pinfunction "G_1") (pintype "passive"))
      (node (ref "R7") (pin "2") (pinfunction "2_2") (pintype "passive"))
    )
    (net (code "100") (name "Net-(Q6-G)") (class "Default")
      (node (ref "Q6") (pin "1") (pinfunction "G_1") (pintype "passive"))
      (node (ref "R8") (pin "2") (pinfunction "2_2") (pintype "passive"))
    )
    (net (code "101") (name "Net-(Q7-G)") (class "Default")
      (node (ref "Q7") (pin "1") (pinfunction "G_1") (pintype "passive"))
      (node (ref "R9") (pin "2") (pinfunction "2_2") (pintype "passive"))
    )
    (net (code "102") (name "Net-(Q8-G)") (class "Default")
      (node (ref "Q8") (pin "1") (pinfunction "G_1") (pintype "passive"))
      (node (ref "R10") (pin "2") (pinfunction "2_2") (pintype "passive"))
    )
    (net (code "103") (name "Net-(Q9-G)") (class "Default")
      (node (ref "Q9") (pin "1") (pinfunction "G_1") (pintype "passive"))
      (node (ref "R11") (pin "2") (pinfunction "2_2") (pintype "passive"))
    )
    (net (code "104") (name "Net-(Q10-G)") (class "Default")
      (node (ref "Q10") (pin "1") (pinfunction "G_1") (pintype "passive"))
      (node (ref "R12") (pin "2") (pinfunction "2_2") (pintype "passive"))
    )
    (net (code "105") (name "Net-(Q11-G)") (class "Default")
      (node (ref "Q11") (pin "1") (pinfunction "G_1") (pintype "passive"))
      (node (ref "R13") (pin "2") (pinfunction "2_2") (pintype "passive"))
    )
    (net (code "106") (name "Net-(Q12-G)") (class "Default")
      (node (ref "Q12") (pin "1") (pinfunction "G_1") (pintype "passive"))
      (node (ref "R14") (pin "2") (pinfunction "2_2") (pintype "passive"))
    )
    (net (code "107") (name "Net-(Q13-G)") (class "Default")
      (node (ref "Q13") (pin "1") (pinfunction "G_1") (pintype "passive"))
      (node (ref "R15") (pin "2") (pinfunction "2_2") (pintype "passive"))
    )
    (net (code "108") (name "Net-(Q14-G)") (class "Default")
      (node (ref "Q14") (pin "1") (pinfunction "G_1") (pintype "passive"))
      (node (ref "R16") (pin "2") (pinfunction "2_2") (pintype "passive"))
    )
    (net (code "109") (name "Net-(Q15-G)") (class "Default")
      (node (ref "Q15") (pin "1") (pinfunction "G_1") (pintype "passive"))
      (node (ref "R17") (pin "2") (pinfunction "2_2") (pintype "passive"))
    )
    (net (code "110") (name "Net-(Q16-G)") (class "Default")
      (node (ref "Q16") (pin "1") (pinfunction "G_1") (pintype "passive"))
      (node (ref "R18") (pin "2") (pinfunction "2_2") (pintype "passive"))
    )
    (net (code "111") (name "Net-(RN1B-1)") (class "Default")
      (node (ref "JP14") (pin "2") (pinfunction "2_2") (pintype "passive"))
      (node (ref "JP2") (pin "2") (pinfunction "2_2") (pintype "passive"))
      (node (ref "RN1") (pin "2") (pinfunction "1_2") (pintype "passive"))
      (node (ref "RN2") (pin "8") (pinfunction "8_8") (pintype "passive"))
    )
    (net (code "112") (name "Net-(RN1C-1)") (class "Default")
      (node (ref "JP14") (pin "3") (pinfunction "3_3") (pintype "passive"))
      (node (ref "JP2") (pin "3") (pinfunction "3_3") (pintype "passive"))
      (node (ref "RN1") (pin "3") (pinfunction "1_3") (pintype "passive"))
      (node (ref "RN2") (pin "7") (pinfunction "7_7") (pintype "passive"))
    )
    (net (code "113") (name "Net-(RN1D-1)") (class "Default")
      (node (ref "JP14") (pin "4") (pinfunction "4_4") (pintype "passive"))
      (node (ref "JP2") (pin "4") (pinfunction "4_4") (pintype "passive"))
      (node (ref "RN1") (pin "4") (pinfunction "1_4") (pintype "passive"))
      (node (ref "RN2") (pin "6") (pinfunction "6_6") (pintype "passive"))
    )
    (net (code "114") (name "Net-(RN1E-1)") (class "Default")
      (node (ref "JP14") (pin "7") (pinfunction "7_7") (pintype "passive"))
      (node (ref "JP2") (pin "5") (pinfunction "5_5") (pintype "passive"))
      (node (ref "RN1") (pin "5") (pinfunction "1_5") (pintype "passive"))
      (node (ref "RN2") (pin "5") (pinfunction "5_5") (pintype "passive"))
    )
    (net (code "115") (name "Net-(RN1F-1)") (class "Default")
      (node (ref "JP14") (pin "8") (pinfunction "8_8") (pintype "passive"))
      (node (ref "JP2") (pin "6") (pinfunction "6_6") (pintype "passive"))
      (node (ref "RN1") (pin "6") (pinfunction "1_6") (pintype "passive"))
      (node (ref "RN2") (pin "4") (pinfunction "4_4") (pintype "passive"))
    )
    (net (code "116") (name "Net-(RN1G-1)") (class "Default")
      (node (ref "JP14") (pin "9") (pinfunction "9_9") (pintype "passive"))
      (node (ref "JP2") (pin "7") (pinfunction "7_7") (pintype "passive"))
      (node (ref "RN1") (pin "7") (pinfunction "1_7") (pintype "passive"))
      (node (ref "RN2") (pin "3") (pinfunction "3_3") (pintype "passive"))
    )
    (net (code "117") (name "Net-(RN1H-1)") (class "Default")
      (node (ref "JP14") (pin "10") (pinfunction "10_10") (pintype "passive"))
      (node (ref "JP2") (pin "8") (pinfunction "8_8") (pintype "passive"))
      (node (ref "RN1") (pin "8") (pinfunction "1_8") (pintype "passive"))
      (node (ref "RN2") (pin "2") (pinfunction "2_2") (pintype "passive"))
    )
    (net (code "118") (name "Net-(RN4B-1)") (class "Default")
      (node (ref "JP13") (pin "2") (pinfunction "2_2") (pintype "passive"))
      (node (ref "JP3") (pin "2") (pinfunction "2_2") (pintype "passive"))
      (node (ref "RN4") (pin "2") (pinfunction "1_2") (pintype "passive"))
      (node (ref "RN5") (pin "8") (pinfunction "8_8") (pintype "passive"))
    )
    (net (code "119") (name "Net-(RN4C-1)") (class "Default")
      (node (ref "JP13") (pin "3") (pinfunction "3_3") (pintype "passive"))
      (node (ref "JP3") (pin "3") (pinfunction "3_3") (pintype "passive"))
      (node (ref "RN4") (pin "3") (pinfunction "1_3") (pintype "passive"))
      (node (ref "RN5") (pin "7") (pinfunction "7_7") (pintype "passive"))
    )
    (net (code "120") (name "Net-(RN4D-1)") (class "Default")
      (node (ref "JP13") (pin "4") (pinfunction "4_4") (pintype "passive"))
      (node (ref "JP3") (pin "4") (pinfunction "4_4") (pintype "passive"))
      (node (ref "RN4") (pin "4") (pinfunction "1_4") (pintype "passive"))
      (node (ref "RN5") (pin "6") (pinfunction "6_6") (pintype "passive"))
    )
    (net (code "121") (name "Net-(RN4E-1)") (class "Default")
      (node (ref "JP13") (pin "7") (pinfunction "7_7") (pintype "passive"))
      (node (ref "JP3") (pin "5") (pinfunction "5_5") (pintype "passive"))
      (node (ref "RN4") (pin "5") (pinfunction "1_5") (pintype "passive"))
      (node (ref "RN5") (pin "5") (pinfunction "5_5") (pintype "passive"))
    )
    (net (code "122") (name "Net-(RN4F-1)") (class "Default")
      (node (ref "JP13") (pin "8") (pinfunction "8_8") (pintype "passive"))
      (node (ref "JP3") (pin "6") (pinfunction "6_6") (pintype "passive"))
      (node (ref "RN4") (pin "6") (pinfunction "1_6") (pintype "passive"))
      (node (ref "RN5") (pin "4") (pinfunction "4_4") (pintype "passive"))
    )
    (net (code "123") (name "Net-(RN4G-1)") (class "Default")
      (node (ref "JP13") (pin "9") (pinfunction "9_9") (pintype "passive"))
      (node (ref "JP3") (pin "7") (pinfunction "7_7") (pintype "passive"))
      (node (ref "RN4") (pin "7") (pinfunction "1_7") (pintype "passive"))
      (node (ref "RN5") (pin "3") (pinfunction "3_3") (pintype "passive"))
    )
    (net (code "124") (name "Net-(RN4H-1)") (class "Default")
      (node (ref "JP13") (pin "10") (pinfunction "10_10") (pintype "passive"))
      (node (ref "JP3") (pin "8") (pinfunction "8_8") (pintype "passive"))
      (node (ref "RN4") (pin "8") (pinfunction "1_8") (pintype "passive"))
      (node (ref "RN5") (pin "2") (pinfunction "2_2") (pintype "passive"))
    )
    (net (code "125") (name "SCK") (class "Default")
      (node (ref "IC1") (pin "7") (pinfunction "CLK_7") (pintype "input"))
      (node (ref "IC3") (pin "11") (pinfunction "SCK_11") (pintype "input"))
      (node (ref "IC4") (pin "7") (pinfunction "CLK_7") (pintype "input"))
      (node (ref "IC5") (pin "11") (pinfunction "SCK_11") (pintype "input"))
      (node (ref "U$1") (pin "PB3") (pinfunction "PB3_PB3") (pintype "bidirectional"))
    )
    (net (code "126") (name "SLNK1") (class "Default")
      (node (ref "IC3") (pin "14") (pinfunction "SER_14") (pintype "input"))
      (node (ref "IC5") (pin "9") (pinfunction "QH*_9") (pintype "tri_state"))
    )
    (net (code "127") (name "unconnected-(H1-MOUNT-PadB3,3)") (class "Default")
      (node (ref "H1") (pin "B3,3") (pinfunction "MOUNT_B3,3") (pintype "passive"))
    )
    (net (code "128") (name "unconnected-(H2-MOUNT-PadB3,3)") (class "Default")
      (node (ref "H2") (pin "B3,3") (pinfunction "MOUNT_B3,3") (pintype "passive"))
    )
    (net (code "129") (name "unconnected-(H3-MOUNT-PadB3,3)") (class "Default")
      (node (ref "H3") (pin "B3,3") (pinfunction "MOUNT_B3,3") (pintype "passive"))
    )
    (net (code "130") (name "unconnected-(H4-MOUNT-PadB3,3)") (class "Default")
      (node (ref "H4") (pin "B3,3") (pinfunction "MOUNT_B3,3") (pintype "passive"))
    )
    (net (code "131") (name "unconnected-(IC3A-QH*-Pad9)") (class "Default")
      (node (ref "IC3") (pin "9") (pinfunction "QH*_9") (pintype "tri_state"))
    )
    (net (code "132") (name "unconnected-(IC6A-+IN-Pad3)") (class "Default")
      (node (ref "IC6") (pin "3") (pinfunction "+IN_3") (pintype "input"))
    )
    (net (code "133") (name "unconnected-(IC6B-+IN-Pad5)") (class "Default")
      (node (ref "IC6") (pin "5") (pinfunction "+IN_5") (pintype "input"))
    )
    (net (code "134") (name "unconnected-(IC6C-+IN-Pad10)") (class "Default")
      (node (ref "IC6") (pin "10") (pinfunction "+IN_10") (pintype "input"))
    )
    (net (code "135") (name "unconnected-(IC6D-+IN-Pad12)") (class "Default")
      (node (ref "IC6") (pin "12") (pinfunction "+IN_12") (pintype "input"))
    )
    (net (code "136") (name "unconnected-(IC7-RS-Pad8)") (class "Default")
      (node (ref "IC7") (pin "8") (pinfunction "RS_8") (pintype "input"))
    )
    (net (code "137") (name "unconnected-(IC7-VREF-Pad5)") (class "Default")
      (node (ref "IC7") (pin "5") (pinfunction "VREF_5") (pintype "output"))
    )
    (net (code "138") (name "unconnected-(IC9A-+IN-Pad3)") (class "Default")
      (node (ref "IC9") (pin "3") (pinfunction "+IN_3") (pintype "input"))
    )
    (net (code "139") (name "unconnected-(IC9B-+IN-Pad5)") (class "Default")
      (node (ref "IC9") (pin "5") (pinfunction "+IN_5") (pintype "input"))
    )
    (net (code "140") (name "unconnected-(IC9C-+IN-Pad10)") (class "Default")
      (node (ref "IC9") (pin "10") (pinfunction "+IN_10") (pintype "input"))
    )
    (net (code "141") (name "unconnected-(IC9D-+IN-Pad12)") (class "Default")
      (node (ref "IC9") (pin "12") (pinfunction "+IN_12") (pintype "input"))
    )
    (net (code "142") (name "unconnected-(J3-Pad2)") (class "Default")
      (node (ref "J3") (pin "2") (pinfunction "2_2") (pintype "passive"))
    )
    (net (code "143") (name "unconnected-(JP4-Pad1)") (class "Default")
      (node (ref "JP4") (pin "1") (pinfunction "1_1") (pintype "passive"))
    )
    (net (code "144") (name "unconnected-(JP4-Pad2)") (class "Default")
      (node (ref "JP4") (pin "2") (pinfunction "2_2") (pintype "passive"))
    )
    (net (code "145") (name "unconnected-(JP4-Pad3)") (class "Default")
      (node (ref "JP4") (pin "3") (pinfunction "3_3") (pintype "passive"))
    )
    (net (code "146") (name "unconnected-(JP4-Pad4)") (class "Default")
      (node (ref "JP4") (pin "4") (pinfunction "4_4") (pintype "passive"))
    )
    (net (code "147") (name "unconnected-(JP7-Pad1)") (class "Default")
      (node (ref "JP7") (pin "1") (pinfunction "1_1") (pintype "passive"))
    )
    (net (code "148") (name "unconnected-(JP7-Pad2)") (class "Default")
      (node (ref "JP7") (pin "2") (pinfunction "2_2") (pintype "passive"))
    )
    (net (code "149") (name "unconnected-(JP7-Pad3)") (class "Default")
      (node (ref "JP7") (pin "3") (pinfunction "3_3") (pintype "passive"))
    )
    (net (code "150") (name "unconnected-(JP7-Pad4)") (class "Default")
      (node (ref "JP7") (pin "4") (pinfunction "4_4") (pintype "passive"))
    )
    (net (code "151") (name "unconnected-(JP7-Pad5)") (class "Default")
      (node (ref "JP7") (pin "5") (pinfunction "5_5") (pintype "passive"))
    )
    (net (code "152") (name "unconnected-(JP7-Pad6)") (class "Default")
      (node (ref "JP7") (pin "6") (pinfunction "6_6") (pintype "passive"))
    )
    (net (code "153") (name "unconnected-(JP8-Pad1)") (class "Default")
      (node (ref "JP8") (pin "1") (pinfunction "1_1") (pintype "passive"))
    )
    (net (code "154") (name "unconnected-(JP8-Pad2)") (class "Default")
      (node (ref "JP8") (pin "2") (pinfunction "2_2") (pintype "passive"))
    )
    (net (code "155") (name "unconnected-(JP8-Pad3)") (class "Default")
      (node (ref "JP8") (pin "3") (pinfunction "3_3") (pintype "passive"))
    )
    (net (code "156") (name "unconnected-(JP8-Pad4)") (class "Default")
      (node (ref "JP8") (pin "4") (pinfunction "4_4") (pintype "passive"))
    )
    (net (code "157") (name "unconnected-(JP9-Pad1)") (class "Default")
      (node (ref "JP9") (pin "1") (pinfunction "1_1") (pintype "passive"))
    )
    (net (code "158") (name "unconnected-(JP9-Pad2)") (class "Default")
      (node (ref "JP9") (pin "2") (pinfunction "2_2") (pintype "passive"))
    )
    (net (code "159") (name "unconnected-(JP9-Pad3)") (class "Default")
      (node (ref "JP9") (pin "3") (pinfunction "3_3") (pintype "passive"))
    )
    (net (code "160") (name "unconnected-(JP9-Pad4)") (class "Default")
      (node (ref "JP9") (pin "4") (pinfunction "4_4") (pintype "passive"))
    )
    (net (code "161") (name "unconnected-(JP10-Pad1)") (class "Default")
      (node (ref "JP10") (pin "1") (pinfunction "1_1") (pintype "passive"))
    )
    (net (code "162") (name "unconnected-(JP10-Pad2)") (class "Default")
      (node (ref "JP10") (pin "2") (pinfunction "2_2") (pintype "passive"))
    )
    (net (code "163") (name "unconnected-(JP10-Pad3)") (class "Default")
      (node (ref "JP10") (pin "3") (pinfunction "3_3") (pintype "passive"))
    )
    (net (code "164") (name "unconnected-(JP10-Pad4)") (class "Default")
      (node (ref "JP10") (pin "4") (pinfunction "4_4") (pintype "passive"))
    )
    (net (code "165") (name "unconnected-(JP11-Pad1)") (class "Default")
      (node (ref "JP11") (pin "1") (pinfunction "1_1") (pintype "passive"))
    )
    (net (code "166") (name "unconnected-(JP11-Pad2)") (class "Default")
      (node (ref "JP11") (pin "2") (pinfunction "2_2") (pintype "passive"))
    )
    (net (code "167") (name "unconnected-(JP11-Pad3)") (class "Default")
      (node (ref "JP11") (pin "3") (pinfunction "3_3") (pintype "passive"))
    )
    (net (code "168") (name "unconnected-(JP11-Pad4)") (class "Default")
      (node (ref "JP11") (pin "4") (pinfunction "4_4") (pintype "passive"))
    )
    (net (code "169") (name "unconnected-(JP11-Pad5)") (class "Default")
      (node (ref "JP11") (pin "5") (pinfunction "5_5") (pintype "passive"))
    )
    (net (code "170") (name "unconnected-(JP11-Pad6)") (class "Default")
      (node (ref "JP11") (pin "6") (pinfunction "6_6") (pintype "passive"))
    )
    (net (code "171") (name "unconnected-(JP13-Pad5)") (class "Default")
      (node (ref "JP13") (pin "5") (pinfunction "5_5") (pintype "passive"))
    )
    (net (code "172") (name "unconnected-(JP13-Pad6)") (class "Default")
      (node (ref "JP13") (pin "6") (pinfunction "6_6") (pintype "passive"))
    )
    (net (code "173") (name "unconnected-(JP14-Pad5)") (class "Default")
      (node (ref "JP14") (pin "5") (pinfunction "5_5") (pintype "passive"))
    )
    (net (code "174") (name "unconnected-(JP14-Pad6)") (class "Default")
      (node (ref "JP14") (pin "6") (pinfunction "6_6") (pintype "passive"))
    )
    (net (code "175") (name "unconnected-(JP15-Pad5)") (class "Default")
      (node (ref "JP15") (pin "5") (pinfunction "5_5") (pintype "passive"))
    )
    (net (code "176") (name "unconnected-(JP15-Pad6)") (class "Default")
      (node (ref "JP15") (pin "6") (pinfunction "6_6") (pintype "passive"))
    )
    (net (code "177") (name "unconnected-(U$1-PadBOOT0)") (class "Default")
      (node (ref "U$1") (pin "BOOT0") (pinfunction "BOOT0_BOOT0") (pintype "bidirectional"))
    )
    (net (code "178") (name "unconnected-(U$1-PadIOREF2)") (class "Default")
      (node (ref "U$1") (pin "IOREF2") (pinfunction "IOREF2_IOREF2") (pintype "input"))
    )
    (net (code "179") (name "unconnected-(U$1-PadNC1-PF7)") (class "Default")
      (node (ref "U$1") (pin "NC1-PF7") (pinfunction "NC1-PF7_NC1-PF7") (pintype "bidirectional"))
    )
    (net (code "180") (name "unconnected-(U$1-PadNC2-PF6)") (class "Default")
      (node (ref "U$1") (pin "NC2-PF6") (pinfunction "NC2-PF6_NC2-PF6") (pintype "bidirectional"))
    )
    (net (code "181") (name "unconnected-(U$1-PadNC3)") (class "Default")
      (node (ref "U$1") (pin "NC3") (pinfunction "NC3_NC3") (pintype "no_connect"))
    )
    (net (code "182") (name "unconnected-(U$1-PadNC4)") (class "Default")
      (node (ref "U$1") (pin "NC4") (pinfunction "NC4_NC4") (pintype "no_connect"))
    )
    (net (code "183") (name "unconnected-(U$1-PadNC5-PD8)") (class "Default")
      (node (ref "U$1") (pin "NC5-PD8") (pinfunction "NC5-PD8_NC5-PD8") (pintype "bidirectional"))
    )
    (net (code "184") (name "unconnected-(U$1-PadNC6-PB11)") (class "Default")
      (node (ref "U$1") (pin "NC6-PB11") (pinfunction "NC6-PB11_NC6-PB11") (pintype "no_connect"))
    )
    (net (code "185") (name "unconnected-(U$1-PadNC7-PF5)") (class "Default")
      (node (ref "U$1") (pin "NC7-PF5") (pinfunction "NC7-PF5_NC7-PF5") (pintype "bidirectional"))
    )
    (net (code "186") (name "unconnected-(U$1-PadNC8-PF4)") (class "Default")
      (node (ref "U$1") (pin "NC8-PF4") (pinfunction "NC8-PF4_NC8-PF4") (pintype "bidirectional"))
    )
    (net (code "187") (name "unconnected-(U$1-PadNRESET)") (class "Default")
      (node (ref "U$1") (pin "NRESET") (pinfunction "NRESET_NRESET") (pintype "input"))
    )
    (net (code "188") (name "unconnected-(U$1-PadPA0)") (class "Default")
      (node (ref "U$1") (pin "PA0") (pinfunction "PA0_PA0") (pintype "bidirectional"))
    )
    (net (code "189") (name "unconnected-(U$1-PadPA1)") (class "Default")
      (node (ref "U$1") (pin "PA1") (pinfunction "PA1_PA1") (pintype "bidirectional"))
    )
    (net (code "190") (name "unconnected-(U$1-PadPA2)") (class "Default")
      (node (ref "U$1") (pin "PA2") (pinfunction "PA2_PA2") (pintype "bidirectional"))
    )
    (net (code "191") (name "unconnected-(U$1-PadPA3)") (class "Default")
      (node (ref "U$1") (pin "PA3") (pinfunction "PA3_PA3") (pintype "bidirectional"))
    )
    (net (code "192") (name "unconnected-(U$1-PadPA4)") (class "Default")
      (node (ref "U$1") (pin "PA4") (pinfunction "PA4_PA4") (pintype "bidirectional"))
    )
    (net (code "193") (name "unconnected-(U$1-PadPA5)") (class "Default")
      (node (ref "U$1") (pin "PA5") (pinfunction "PA5_PA5") (pintype "bidirectional"))
    )
    (net (code "194") (name "unconnected-(U$1-PadPA6)") (class "Default")
      (node (ref "U$1") (pin "PA6") (pinfunction "PA6_PA6") (pintype "bidirectional"))
    )
    (net (code "195") (name "unconnected-(U$1-PadPA7)") (class "Default")
      (node (ref "U$1") (pin "PA7") (pinfunction "PA7_PA7") (pintype "bidirectional"))
    )
    (net (code "196") (name "unconnected-(U$1-PadPA8)") (class "Default")
      (node (ref "U$1") (pin "PA8") (pinfunction "PA8_PA8") (pintype "bidirectional"))
    )
    (net (code "197") (name "unconnected-(U$1-PadPA9)") (class "Default")
      (node (ref "U$1") (pin "PA9") (pinfunction "PA9_PA9") (pintype "bidirectional"))
    )
    (net (code "198") (name "unconnected-(U$1-PadPA10)") (class "Default")
      (node (ref "U$1") (pin "PA10") (pinfunction "PA10_PA10") (pintype "bidirectional"))
    )
    (net (code "199") (name "unconnected-(U$1-PadPA11)") (class "Default")
      (node (ref "U$1") (pin "PA11") (pinfunction "PA11_PA11") (pintype "bidirectional"))
    )
    (net (code "200") (name "unconnected-(U$1-PadPA12)") (class "Default")
      (node (ref "U$1") (pin "PA12") (pinfunction "PA12_PA12") (pintype "bidirectional"))
    )
    (net (code "201") (name "unconnected-(U$1-PadPA13)") (class "Default")
      (node (ref "U$1") (pin "PA13") (pinfunction "PA13_PA13") (pintype "bidirectional"))
    )
    (net (code "202") (name "unconnected-(U$1-PadPA14)") (class "Default")
      (node (ref "U$1") (pin "PA14") (pinfunction "PA14_PA14") (pintype "bidirectional"))
    )
    (net (code "203") (name "unconnected-(U$1-PadPA15)") (class "Default")
      (node (ref "U$1") (pin "PA15") (pinfunction "PA15_PA15") (pintype "bidirectional"))
    )
    (net (code "204") (name "unconnected-(U$1-PadPB0)") (class "Default")
      (node (ref "U$1") (pin "PB0") (pinfunction "PB0_PB0") (pintype "bidirectional"))
    )
    (net (code "205") (name "unconnected-(U$1-PadPB1)") (class "Default")
      (node (ref "U$1") (pin "PB1") (pinfunction "PB1_PB1") (pintype "bidirectional"))
    )
    (net (code "206") (name "unconnected-(U$1-PadPB2)") (class "Default")
      (node (ref "U$1") (pin "PB2") (pinfunction "PB2_PB2") (pintype "bidirectional"))
    )
    (net (code "207") (name "unconnected-(U$1-PadPB6)") (class "Default")
      (node (ref "U$1") (pin "PB6") (pinfunction "PB6_PB6") (pintype "bidirectional"))
    )
    (net (code "208") (name "unconnected-(U$1-PadPB7)") (class "Default")
      (node (ref "U$1") (pin "PB7") (pinfunction "PB7_PB7") (pintype "bidirectional"))
    )
    (net (code "209") (name "unconnected-(U$1-PadPB10)") (class "Default")
      (node (ref "U$1") (pin "PB10") (pinfunction "PB10_PB10") (pintype "bidirectional"))
    )
    (net (code "210") (name "unconnected-(U$1-PadPB12)") (class "Default")
      (node (ref "U$1") (pin "PB12") (pinfunction "PB12_PB12") (pintype "bidirectional"))
    )
    (net (code "211") (name "unconnected-(U$1-PadPB13)") (class "Default")
      (node (ref "U$1") (pin "PB13") (pinfunction "PB13_PB13") (pintype "bidirectional"))
    )
    (net (code "212") (name "unconnected-(U$1-PadPB14)") (class "Default")
      (node (ref "U$1") (pin "PB14") (pinfunction "PB14_PB14") (pintype "bidirectional"))
    )
    (net (code "213") (name "unconnected-(U$1-PadPB15)") (class "Default")
      (node (ref "U$1") (pin "PB15") (pinfunction "PB15_PB15") (pintype "bidirectional"))
    )
    (net (code "214") (name "unconnected-(U$1-PadPC0)") (class "Default")
      (node (ref "U$1") (pin "PC0") (pinfunction "PC0_PC0") (pintype "bidirectional"))
    )
    (net (code "215") (name "unconnected-(U$1-PadPC1)") (class "Default")
      (node (ref "U$1") (pin "PC1") (pinfunction "PC1_PC1") (pintype "bidirectional"))
    )
    (net (code "216") (name "unconnected-(U$1-PadPC2)") (class "Default")
      (node (ref "U$1") (pin "PC2") (pinfunction "PC2_PC2") (pintype "bidirectional"))
    )
    (net (code "217") (name "unconnected-(U$1-PadPC3)") (class "Default")
      (node (ref "U$1") (pin "PC3") (pinfunction "PC3_PC3") (pintype "bidirectional"))
    )
    (net (code "218") (name "unconnected-(U$1-PadPC4)") (class "Default")
      (node (ref "U$1") (pin "PC4") (pinfunction "PC4_PC4") (pintype "bidirectional"))
    )
    (net (code "219") (name "unconnected-(U$1-PadPC5)") (class "Default")
      (node (ref "U$1") (pin "PC5") (pinfunction "PC5_PC5") (pintype "bidirectional"))
    )
    (net (code "220") (name "unconnected-(U$1-PadPC6)") (class "Default")
      (node (ref "U$1") (pin "PC6") (pinfunction "PC6_PC6") (pintype "bidirectional"))
    )
    (net (code "221") (name "unconnected-(U$1-PadPC7)") (class "Default")
      (node (ref "U$1") (pin "PC7") (pinfunction "PC7_PC7") (pintype "bidirectional"))
    )
    (net (code "222") (name "unconnected-(U$1-PadPC8)") (class "Default")
      (node (ref "U$1") (pin "PC8") (pinfunction "PC8_PC8") (pintype "bidirectional"))
    )
    (net (code "223") (name "unconnected-(U$1-PadPC9)") (class "Default")
      (node (ref "U$1") (pin "PC9") (pinfunction "PC9_PC9") (pintype "bidirectional"))
    )
    (net (code "224") (name "unconnected-(U$1-PadPC10)") (class "Default")
      (node (ref "U$1") (pin "PC10") (pinfunction "PC10_PC10") (pintype "bidirectional"))
    )
    (net (code "225") (name "unconnected-(U$1-PadPC11)") (class "Default")
      (node (ref "U$1") (pin "PC11") (pinfunction "PC11_PC11") (pintype "bidirectional"))
    )
    (net (code "226") (name "unconnected-(U$1-PadPC12)") (class "Default")
      (node (ref "U$1") (pin "PC12") (pinfunction "PC12_PC12") (pintype "bidirectional"))
    )
    (net (code "227") (name "unconnected-(U$1-PadPC13)") (class "Default")
      (node (ref "U$1") (pin "PC13") (pinfunction "PC13_PC13") (pintype "bidirectional"))
    )
    (net (code "228") (name "unconnected-(U$1-PadPC14)") (class "Default")
      (node (ref "U$1") (pin "PC14") (pinfunction "PC14_PC14") (pintype "bidirectional"))
    )
    (net (code "229") (name "unconnected-(U$1-PadPC15)") (class "Default")
      (node (ref "U$1") (pin "PC15") (pinfunction "PC15_PC15") (pintype "bidirectional"))
    )
    (net (code "230") (name "unconnected-(U$1-PadPD2)") (class "Default")
      (node (ref "U$1") (pin "PD2") (pinfunction "PD2_PD2") (pintype "bidirectional"))
    )
    (net (code "231") (name "unconnected-(U$1-PadPF0-PH0)") (class "Default")
      (node (ref "U$1") (pin "PF0-PH0") (pinfunction "PF0-PH0_PF0-PH0") (pintype "bidirectional"))
    )
    (net (code "232") (name "unconnected-(U$1-PadPF1-PH1)") (class "Default")
      (node (ref "U$1") (pin "PF1-PH1") (pinfunction "PF1-PH1_PF1-PH1") (pintype "bidirectional"))
    )
  )
)
